# MotionDetectorCamera.net
KiCad netlist of a schematic drawn in EAGLE
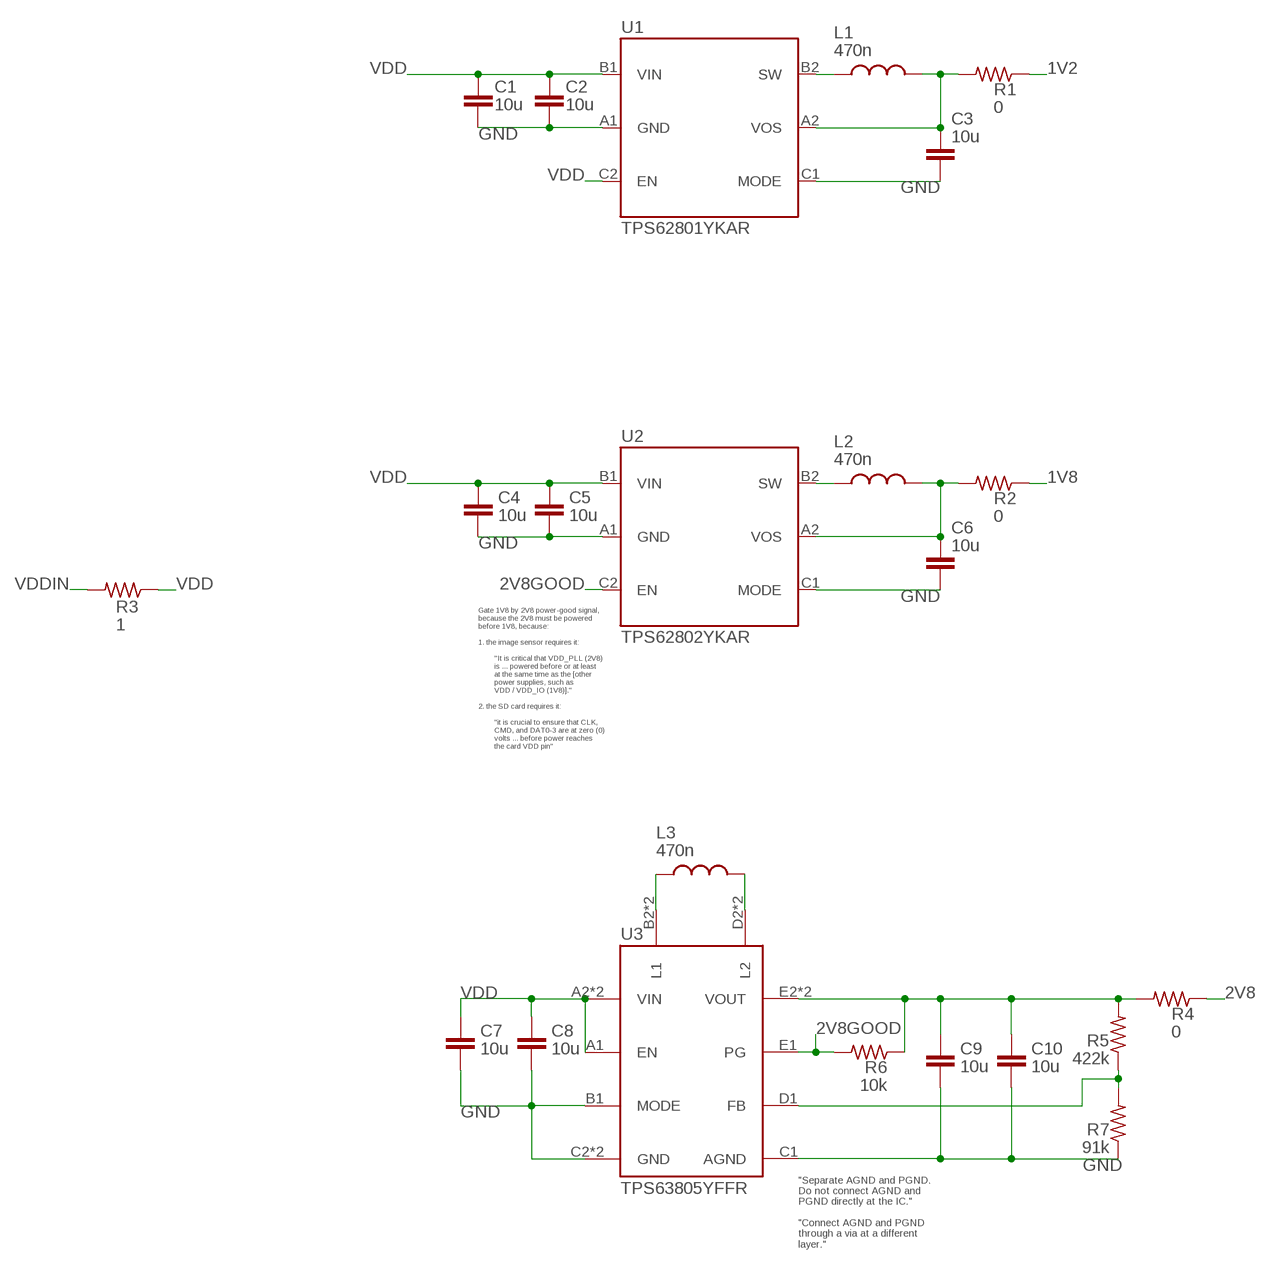
[diagram p0: schematic, sheet 1]
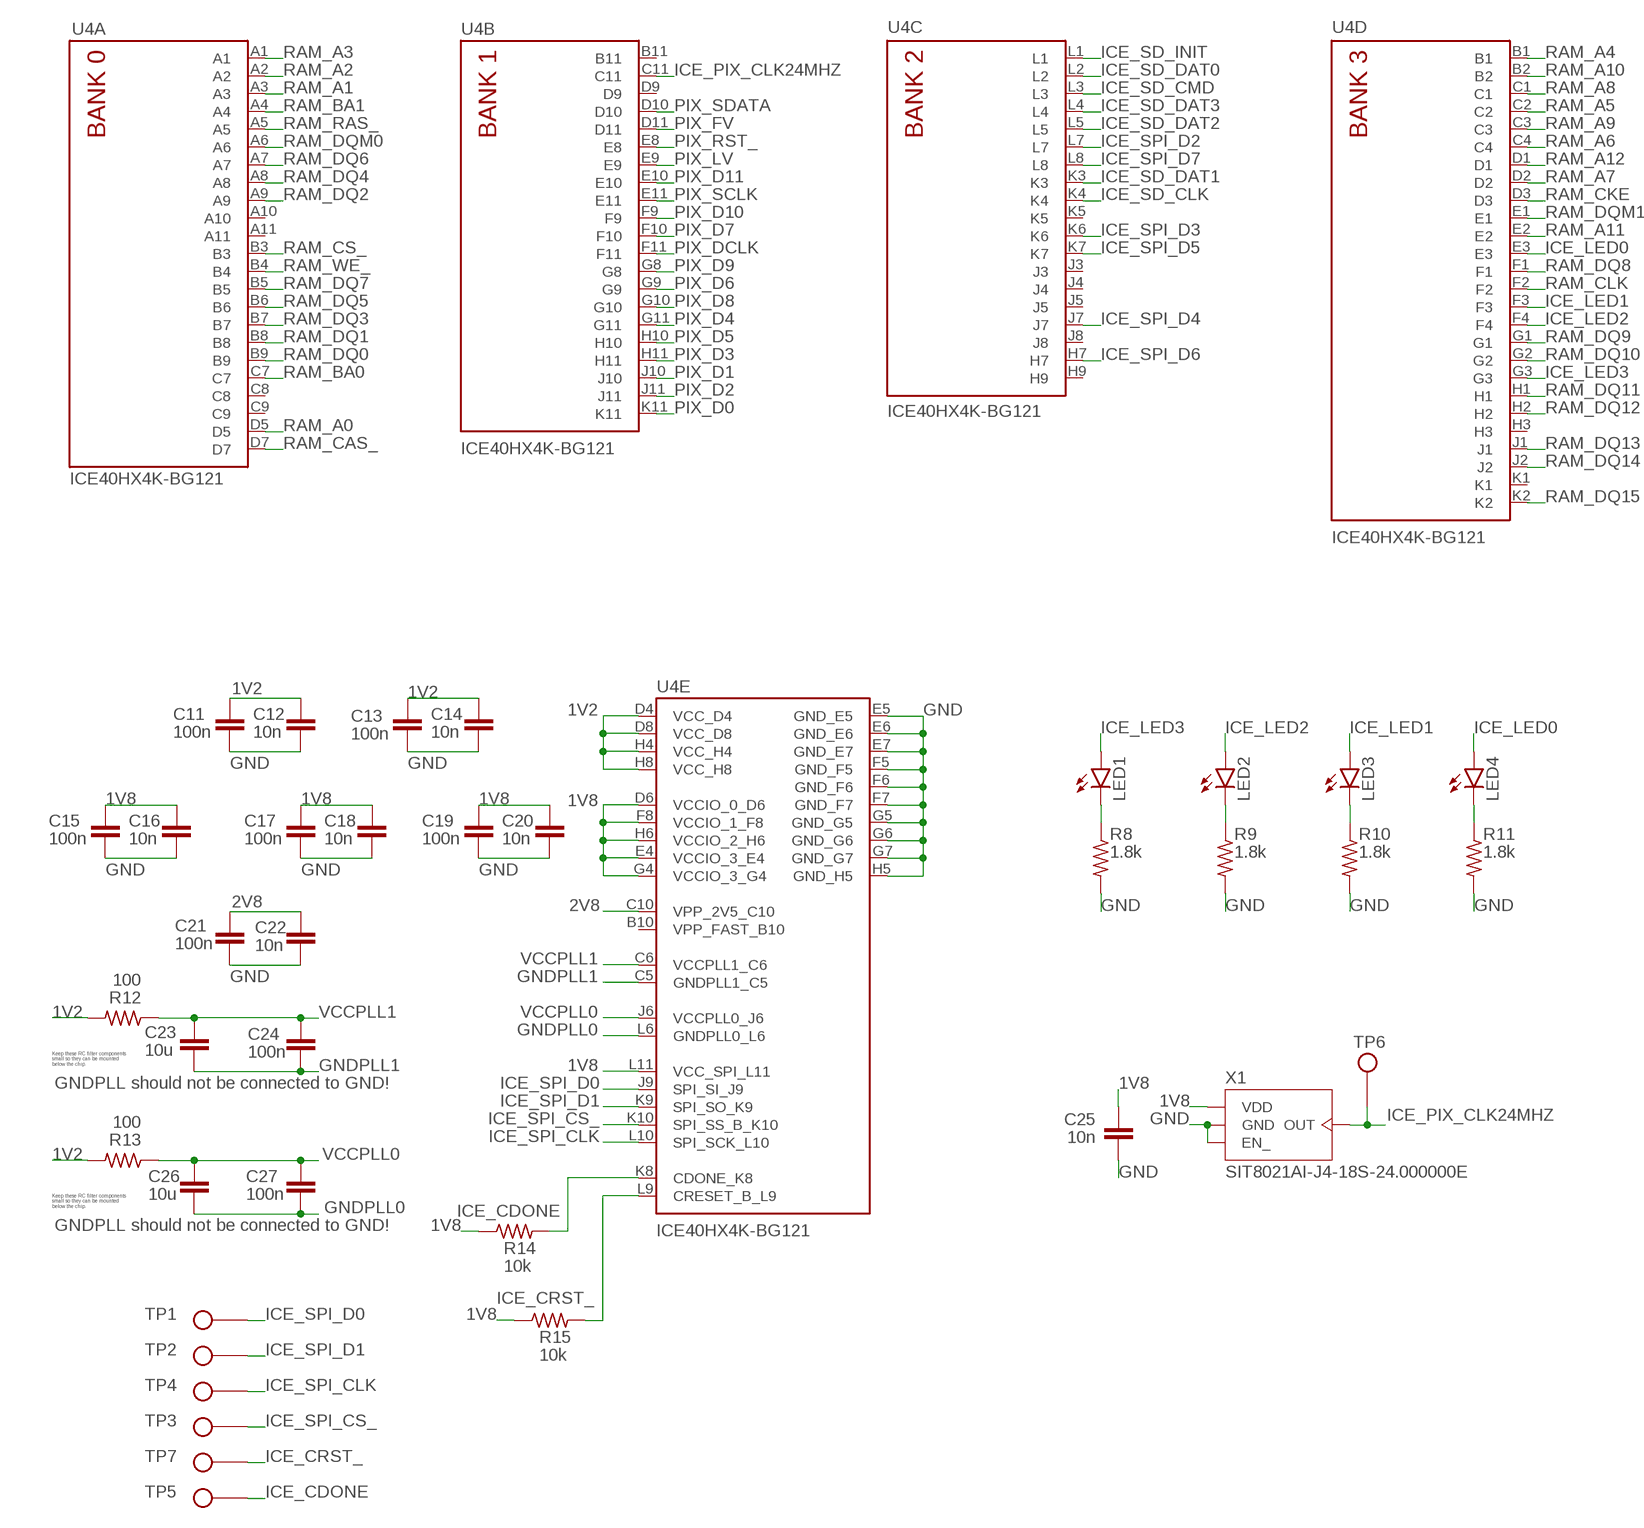
[diagram p1: schematic, sheet 2]
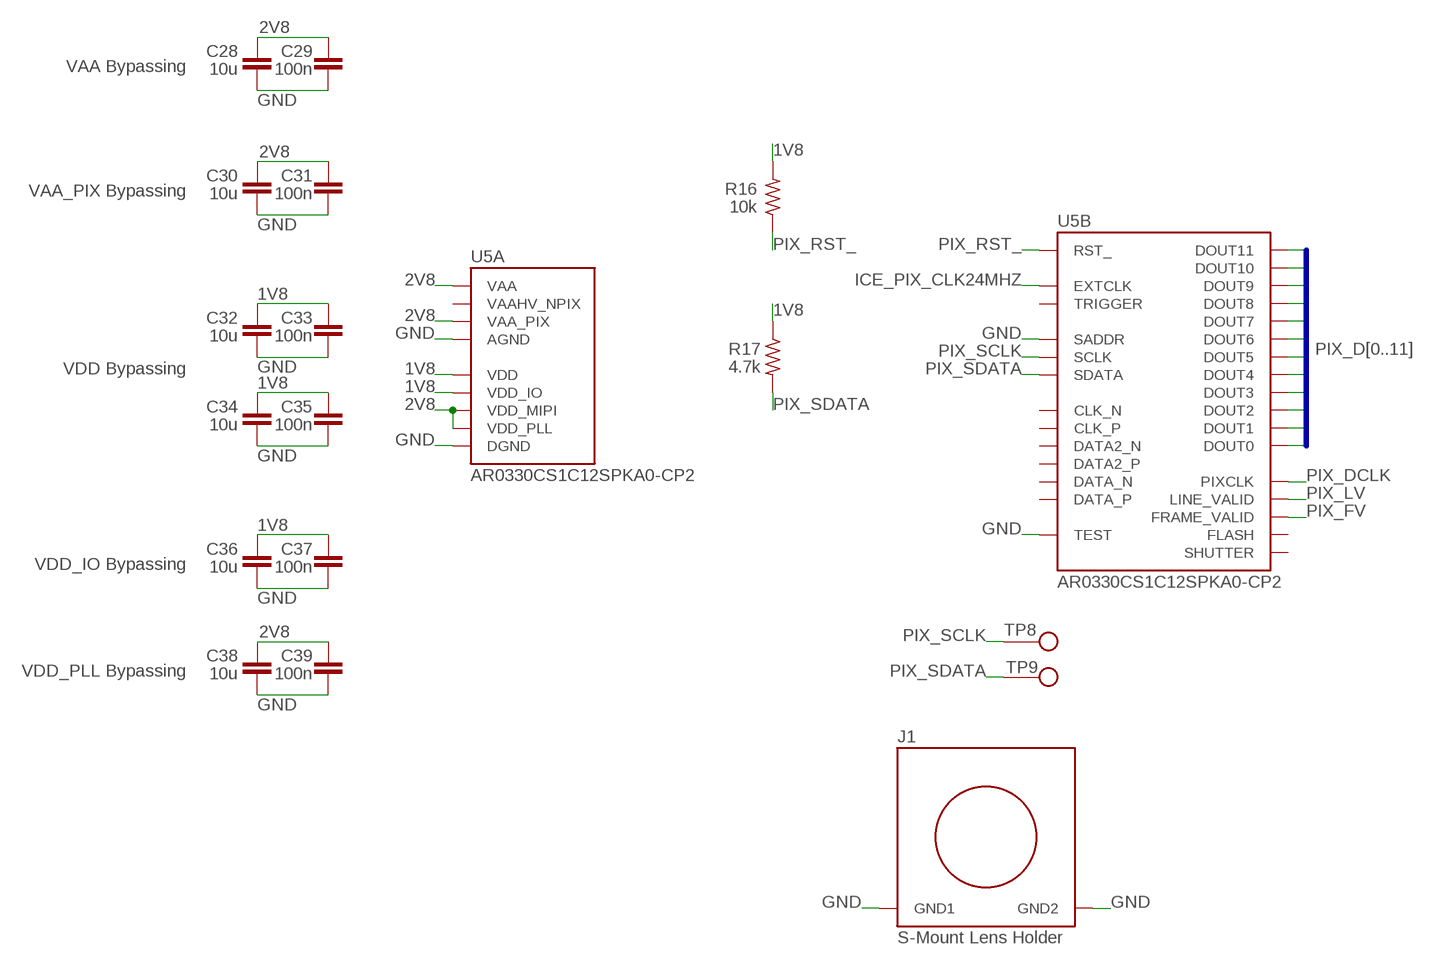
[diagram p2: schematic, sheet 3]
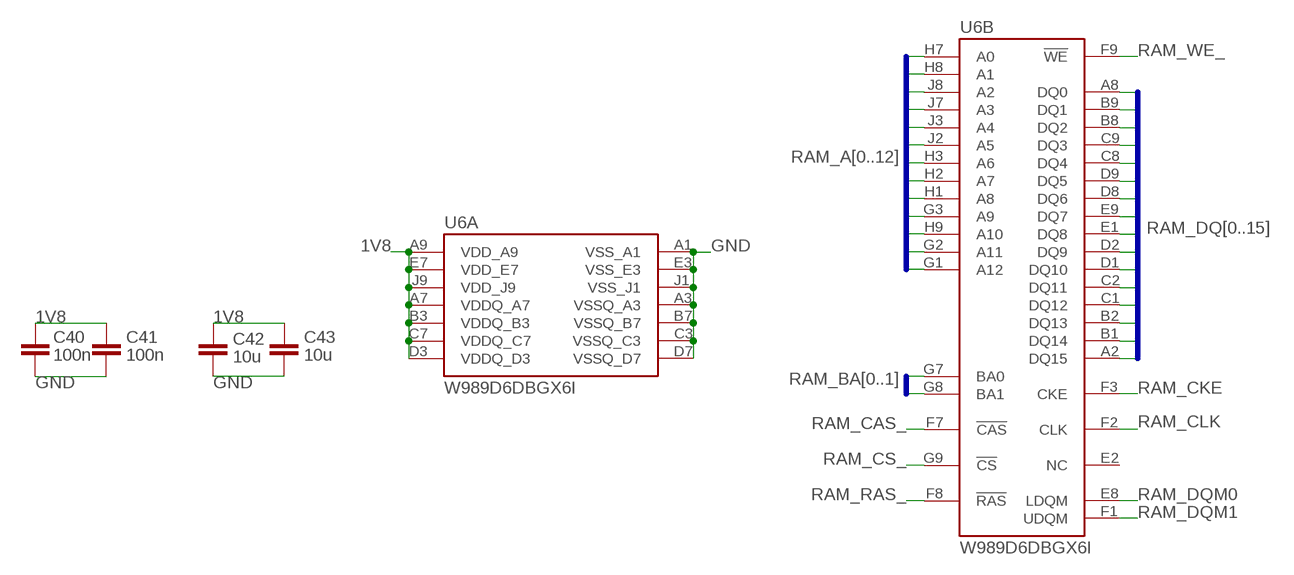
[diagram p3: schematic, sheet 4]
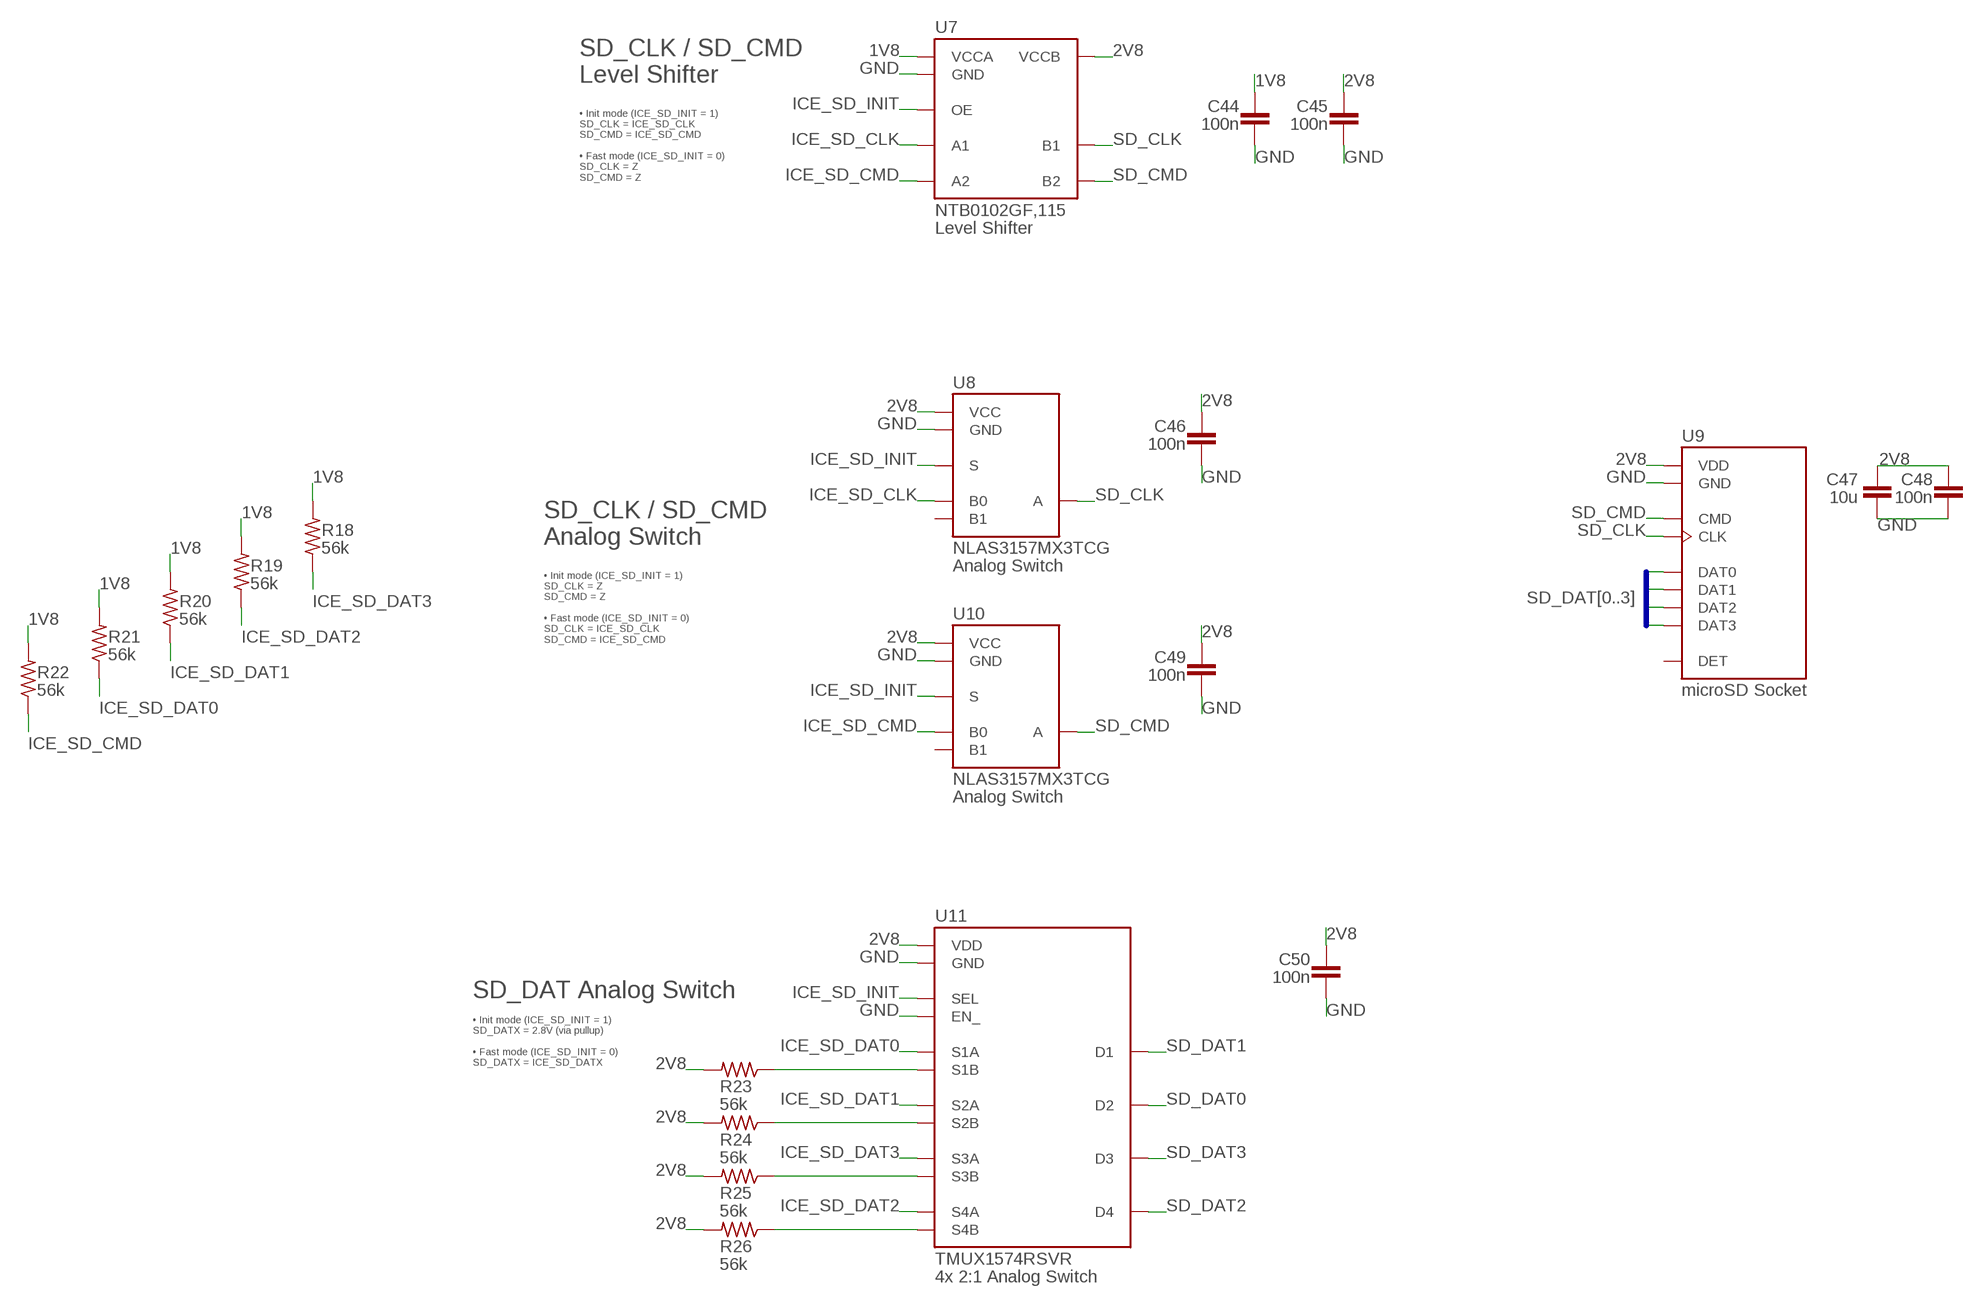
[diagram p4: schematic, sheet 5]
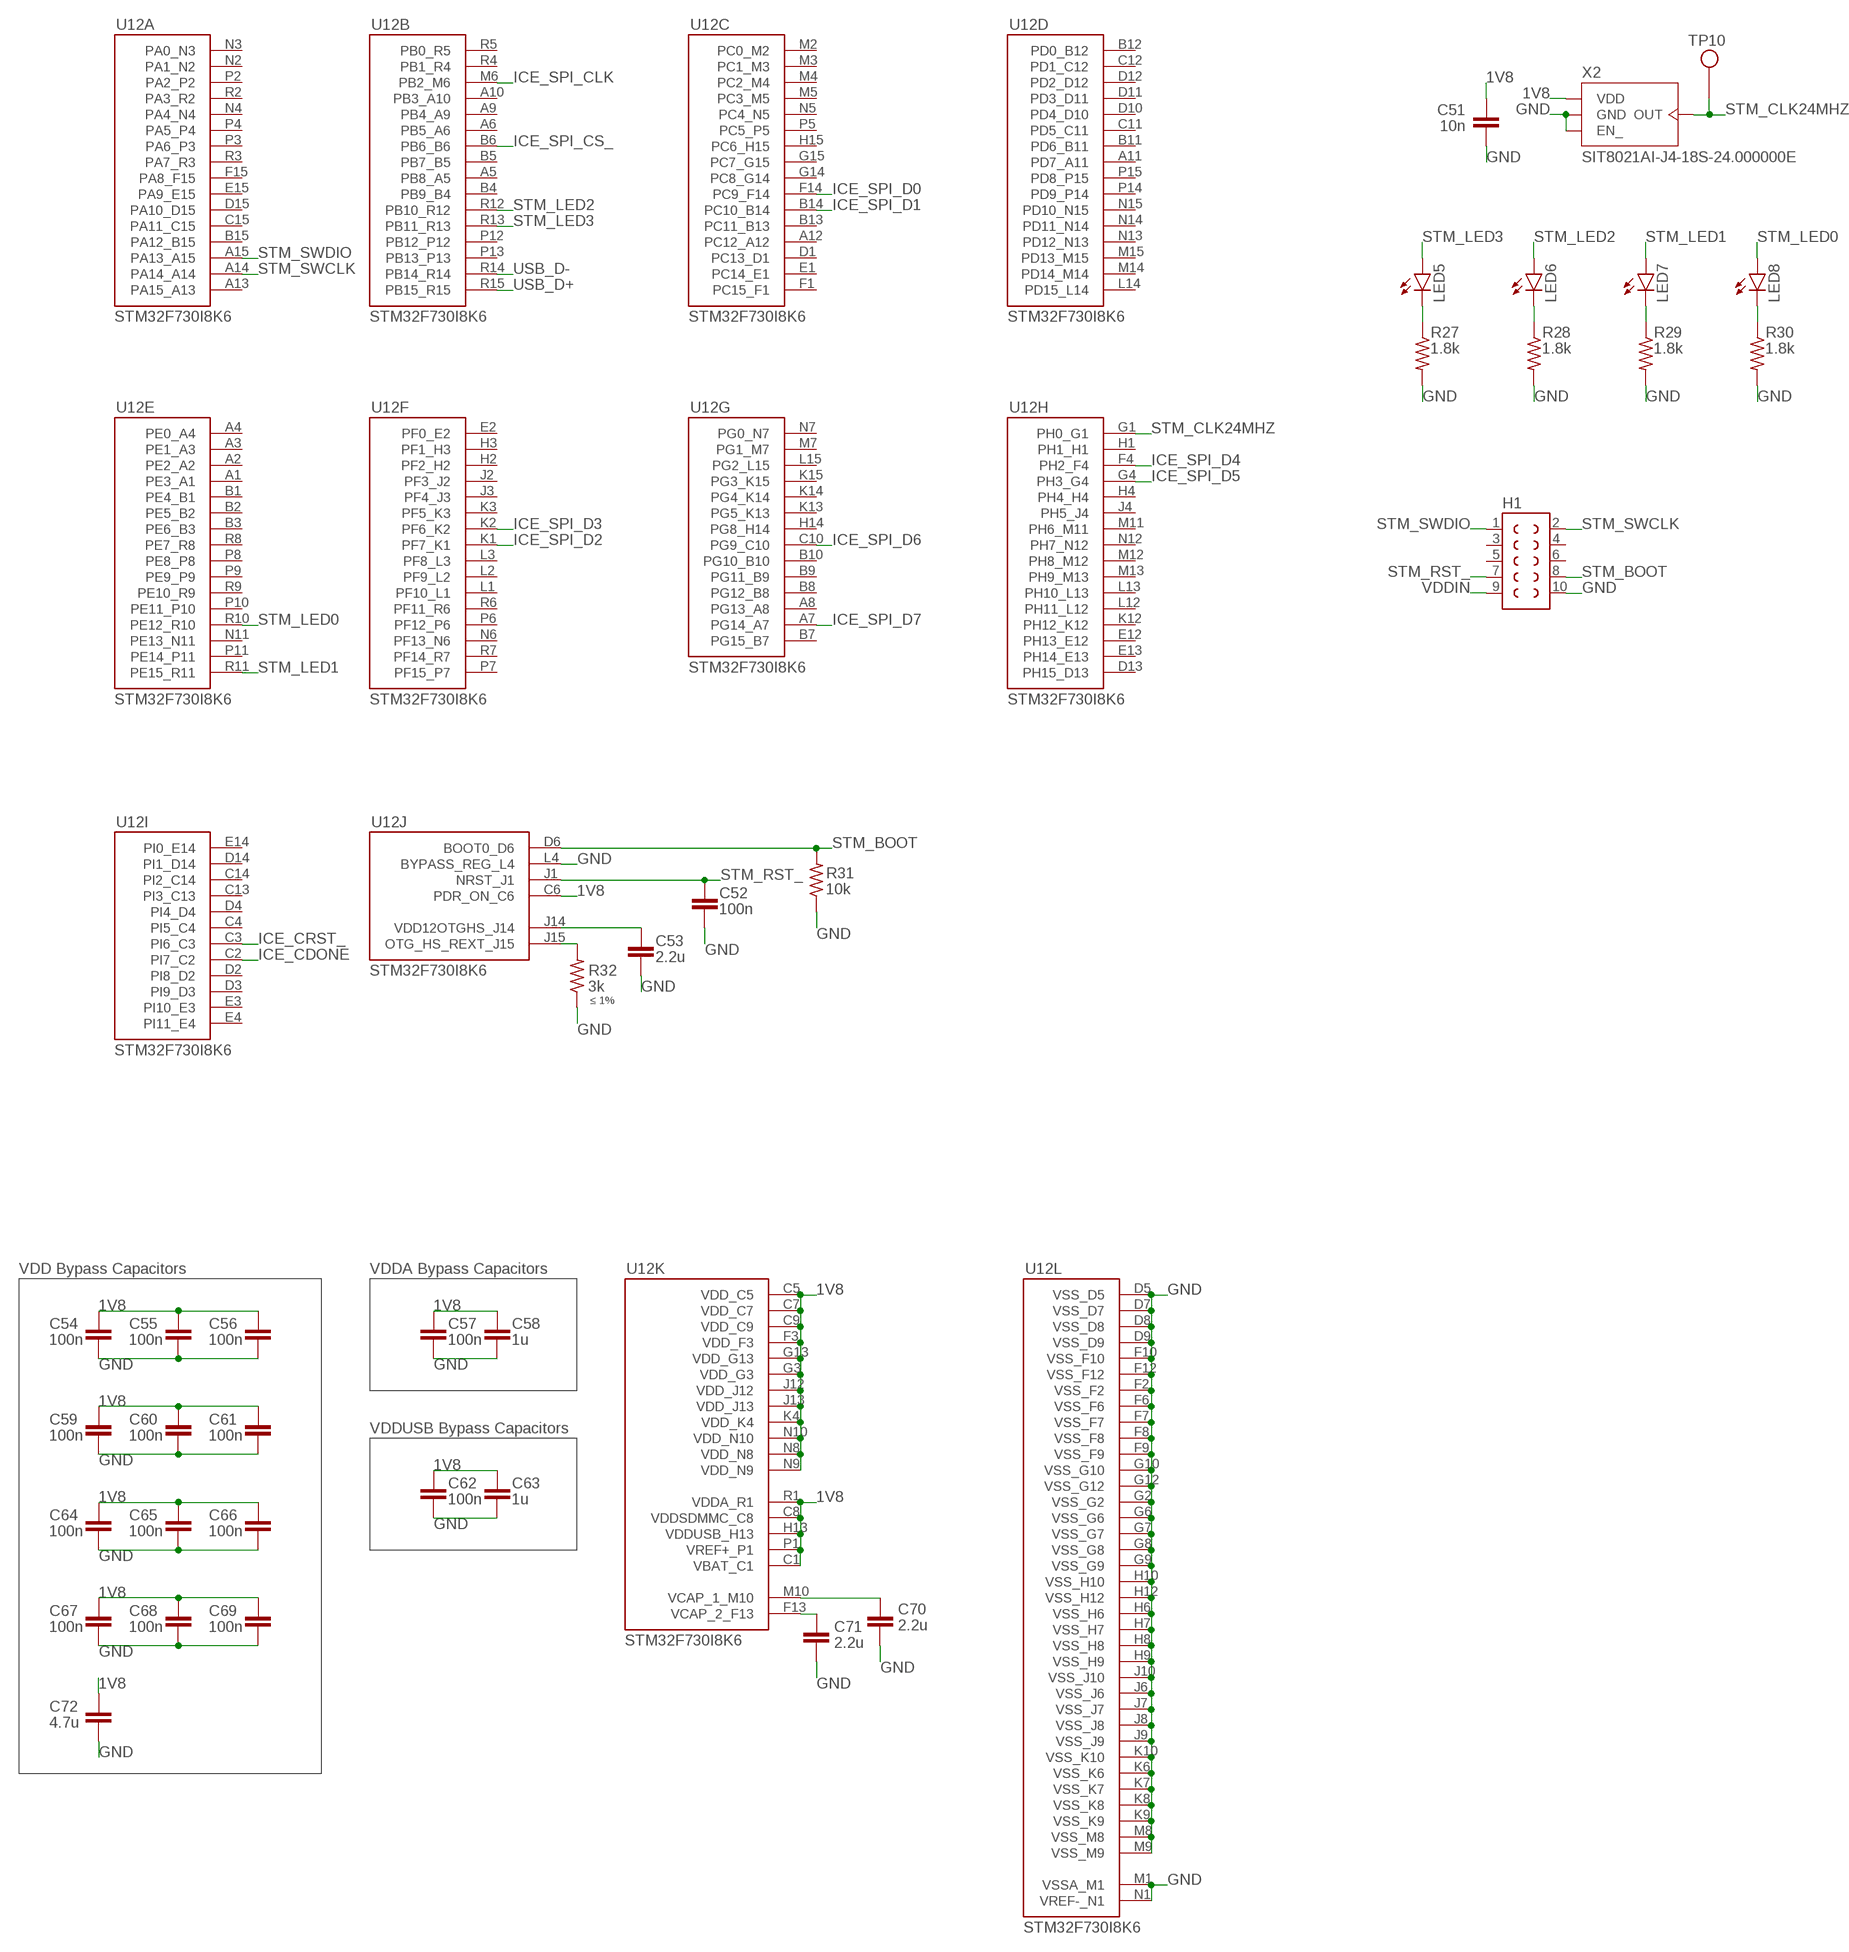
[diagram p5: schematic, sheet 6]
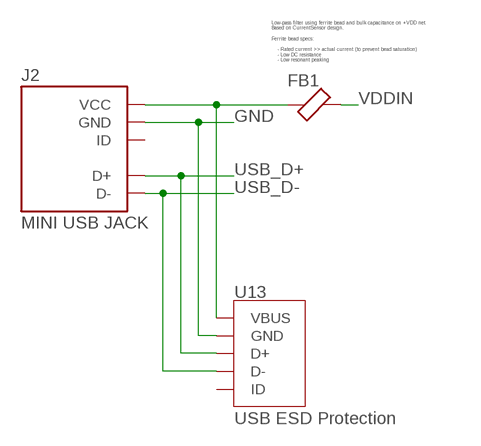
[diagram p6: schematic, sheet 7]

(export (version "E")
  (design (tool "Eeschema 10.0.6"))
  (components
    (comp (ref "C40")
      (value "100n")
      (footprint "eagle-import:0402")
      (fields (field (name "MFG") "Murata"))
      (libsource (lib "eagle-import") (part "CAPACITOR0402"))
    )
    (comp (ref "C41")
      (value "100n")
      (footprint "eagle-import:0402")
      (fields (field (name "MFG") "Murata"))
      (libsource (lib "eagle-import") (part "CAPACITOR0402"))
    )
    (comp (ref "C42")
      (value "10u")
      (footprint "eagle-import:0805")
      (fields (field (name "MFG") "KEMET"))
      (libsource (lib "eagle-import") (part "CAPACITOR0805"))
    )
    (comp (ref "C43")
      (value "10u")
      (footprint "eagle-import:0805")
      (fields (field (name "MFG") "KEMET"))
      (libsource (lib "eagle-import") (part "CAPACITOR0805"))
    )
    (comp (ref "U6")
      (value "W989D6DBGX6I")
      (footprint "eagle-import:W989D6DBGX6I")
      (fields (field (name "PN") "W989D6DBGX6I") (field (name "MFG") "Winbond"))
      (libsource (lib "eagle-import") (part "W989D6DBGX6I"))
    )
    (comp (ref "C11")
      (value "100n")
      (footprint "eagle-import:0402")
      (fields (field (name "MFG") "Murata"))
      (libsource (lib "eagle-import") (part "CAPACITOR0402"))
    )
    (comp (ref "C12")
      (value "10n")
      (footprint "eagle-import:0402")
      (fields (field (name "MFG") "Murata"))
      (libsource (lib "eagle-import") (part "CAPACITOR0402"))
    )
    (comp (ref "C13")
      (value "100n")
      (footprint "eagle-import:0402")
      (fields (field (name "MFG") "Murata"))
      (libsource (lib "eagle-import") (part "CAPACITOR0402"))
    )
    (comp (ref "C14")
      (value "10n")
      (footprint "eagle-import:0402")
      (fields (field (name "MFG") "Murata"))
      (libsource (lib "eagle-import") (part "CAPACITOR0402"))
    )
    (comp (ref "C15")
      (value "100n")
      (footprint "eagle-import:0402")
      (fields (field (name "MFG") "Murata"))
      (libsource (lib "eagle-import") (part "CAPACITOR0402"))
    )
    (comp (ref "C16")
      (value "10n")
      (footprint "eagle-import:0402")
      (fields (field (name "MFG") "Murata"))
      (libsource (lib "eagle-import") (part "CAPACITOR0402"))
    )
    (comp (ref "C17")
      (value "100n")
      (footprint "eagle-import:0402")
      (fields (field (name "MFG") "Murata"))
      (libsource (lib "eagle-import") (part "CAPACITOR0402"))
    )
    (comp (ref "C18")
      (value "10n")
      (footprint "eagle-import:0402")
      (fields (field (name "MFG") "Murata"))
      (libsource (lib "eagle-import") (part "CAPACITOR0402"))
    )
    (comp (ref "C19")
      (value "100n")
      (footprint "eagle-import:0402")
      (fields (field (name "MFG") "Murata"))
      (libsource (lib "eagle-import") (part "CAPACITOR0402"))
    )
    (comp (ref "C20")
      (value "10n")
      (footprint "eagle-import:0402")
      (fields (field (name "MFG") "Murata"))
      (libsource (lib "eagle-import") (part "CAPACITOR0402"))
    )
    (comp (ref "C21")
      (value "100n")
      (footprint "eagle-import:0402")
      (fields (field (name "MFG") "Murata"))
      (libsource (lib "eagle-import") (part "CAPACITOR0402"))
    )
    (comp (ref "C22")
      (value "10n")
      (footprint "eagle-import:0402")
      (fields (field (name "MFG") "Murata"))
      (libsource (lib "eagle-import") (part "CAPACITOR0402"))
    )
    (comp (ref "C23")
      (value "10u")
      (footprint "eagle-import:0805")
      (fields (field (name "MFG") "KEMET"))
      (libsource (lib "eagle-import") (part "CAPACITOR0805"))
    )
    (comp (ref "C24")
      (value "100n")
      (footprint "eagle-import:0402")
      (fields (field (name "MFG") "Murata"))
      (libsource (lib "eagle-import") (part "CAPACITOR0402"))
    )
    (comp (ref "C25")
      (value "10n")
      (footprint "eagle-import:0402")
      (fields (field (name "MFG") "Murata"))
      (libsource (lib "eagle-import") (part "CAPACITOR0402"))
    )
    (comp (ref "C26")
      (value "10u")
      (footprint "eagle-import:0805")
      (fields (field (name "MFG") "KEMET"))
      (libsource (lib "eagle-import") (part "CAPACITOR0805"))
    )
    (comp (ref "C27")
      (value "100n")
      (footprint "eagle-import:0402")
      (fields (field (name "MFG") "Murata"))
      (libsource (lib "eagle-import") (part "CAPACITOR0402"))
    )
    (comp (ref "LED1")
      (value "LED")
      (footprint "eagle-import:LED-0603")
      (fields (field (name "MFG") "OSRAM"))
      (libsource (lib "eagle-import") (part "LED"))
    )
    (comp (ref "LED2")
      (value "LED")
      (footprint "eagle-import:LED-0603")
      (fields (field (name "MFG") "OSRAM"))
      (libsource (lib "eagle-import") (part "LED"))
    )
    (comp (ref "LED3")
      (value "LED")
      (footprint "eagle-import:LED-0603")
      (fields (field (name "MFG") "OSRAM"))
      (libsource (lib "eagle-import") (part "LED"))
    )
    (comp (ref "LED4")
      (value "LED")
      (footprint "eagle-import:LED-0603")
      (fields (field (name "MFG") "OSRAM"))
      (libsource (lib "eagle-import") (part "LED"))
    )
    (comp (ref "R8")
      (value "1.8k")
      (footprint "eagle-import:0402")
      (fields (field (name "MFG") "TE Connectivity"))
      (libsource (lib "eagle-import") (part "RESISTOR0402"))
    )
    (comp (ref "R9")
      (value "1.8k")
      (footprint "eagle-import:0402")
      (fields (field (name "MFG") "TE Connectivity"))
      (libsource (lib "eagle-import") (part "RESISTOR0402"))
    )
    (comp (ref "R10")
      (value "1.8k")
      (footprint "eagle-import:0402")
      (fields (field (name "MFG") "TE Connectivity"))
      (libsource (lib "eagle-import") (part "RESISTOR0402"))
    )
    (comp (ref "R11")
      (value "1.8k")
      (footprint "eagle-import:0402")
      (fields (field (name "MFG") "TE Connectivity"))
      (libsource (lib "eagle-import") (part "RESISTOR0402"))
    )
    (comp (ref "R12")
      (value "100")
      (footprint "eagle-import:0402")
      (fields (field (name "MFG") "Bourns"))
      (libsource (lib "eagle-import") (part "RESISTOR0402"))
    )
    (comp (ref "R13")
      (value "100")
      (footprint "eagle-import:0402")
      (fields (field (name "MFG") "Bourns"))
      (libsource (lib "eagle-import") (part "RESISTOR0402"))
    )
    (comp (ref "R14")
      (value "10k")
      (footprint "eagle-import:0402")
      (fields (field (name "MFG") "Vishay"))
      (libsource (lib "eagle-import") (part "RESISTOR0402"))
    )
    (comp (ref "R15")
      (value "10k")
      (footprint "eagle-import:0402")
      (fields (field (name "MFG") "Vishay"))
      (libsource (lib "eagle-import") (part "RESISTOR0402"))
    )
    (comp (ref "TP1")
      (value "TEST-POINT")
      (footprint "eagle-import:TEST-POINT")
      (libsource (lib "eagle-import") (part "TEST-POINT"))
    )
    (comp (ref "TP2")
      (value "TEST-POINT")
      (footprint "eagle-import:TEST-POINT")
      (libsource (lib "eagle-import") (part "TEST-POINT"))
    )
    (comp (ref "TP3")
      (value "TEST-POINT")
      (footprint "eagle-import:TEST-POINT")
      (libsource (lib "eagle-import") (part "TEST-POINT"))
    )
    (comp (ref "TP4")
      (value "TEST-POINT")
      (footprint "eagle-import:TEST-POINT")
      (libsource (lib "eagle-import") (part "TEST-POINT"))
    )
    (comp (ref "TP5")
      (value "TEST-POINT")
      (footprint "eagle-import:TEST-POINT")
      (libsource (lib "eagle-import") (part "TEST-POINT"))
    )
    (comp (ref "TP6")
      (value "TEST-POINT")
      (footprint "eagle-import:TEST-POINT")
      (libsource (lib "eagle-import") (part "TEST-POINT"))
    )
    (comp (ref "TP7")
      (value "TEST-POINT")
      (footprint "eagle-import:TEST-POINT")
      (libsource (lib "eagle-import") (part "TEST-POINT"))
    )
    (comp (ref "U4")
      (value "LATTICE-ICE40HX4K-BG121")
      (footprint "eagle-import:LATTICE-ICE40HX4K-BG121")
      (fields (field (name "MFG") "Lattice"))
      (libsource (lib "eagle-import") (part "LATTICE-ICE40HX4K-BG121"))
    )
    (comp (ref "X1")
      (value "SITIME-SIT8021")
      (footprint "eagle-import:SITIME-SIT8021")
      (fields (field (name "MFG") "SiTime") (field (name "PN") "SIT8021AI-J4-18S-24.000000E"))
      (libsource (lib "eagle-import") (part "SITIME-SIT8021"))
    )
    (comp (ref "C51")
      (value "10n")
      (footprint "eagle-import:0402")
      (fields (field (name "MFG") "Murata"))
      (libsource (lib "eagle-import") (part "CAPACITOR0402"))
    )
    (comp (ref "C52")
      (value "100n")
      (footprint "eagle-import:0402")
      (fields (field (name "MFG") "Murata"))
      (libsource (lib "eagle-import") (part "CAPACITOR0402"))
    )
    (comp (ref "C53")
      (value "2.2u")
      (footprint "eagle-import:0402")
      (fields (field (name "MFG") "AVX"))
      (libsource (lib "eagle-import") (part "CAPACITOR0402"))
    )
    (comp (ref "C54")
      (value "100n")
      (footprint "eagle-import:0402")
      (fields (field (name "MFG") "Murata"))
      (libsource (lib "eagle-import") (part "CAPACITOR0402"))
    )
    (comp (ref "C55")
      (value "100n")
      (footprint "eagle-import:0402")
      (fields (field (name "MFG") "Murata"))
      (libsource (lib "eagle-import") (part "CAPACITOR0402"))
    )
    (comp (ref "C56")
      (value "100n")
      (footprint "eagle-import:0402")
      (fields (field (name "MFG") "Murata"))
      (libsource (lib "eagle-import") (part "CAPACITOR0402"))
    )
    (comp (ref "C57")
      (value "100n")
      (footprint "eagle-import:0402")
      (fields (field (name "MFG") "Murata"))
      (libsource (lib "eagle-import") (part "CAPACITOR0402"))
    )
    (comp (ref "C58")
      (value "1u")
      (footprint "eagle-import:0402")
      (fields (field (name "MFG") "Taiyo Yuden"))
      (libsource (lib "eagle-import") (part "CAPACITOR0402"))
    )
    (comp (ref "C59")
      (value "100n")
      (footprint "eagle-import:0402")
      (fields (field (name "MFG") "Murata"))
      (libsource (lib "eagle-import") (part "CAPACITOR0402"))
    )
    (comp (ref "C60")
      (value "100n")
      (footprint "eagle-import:0402")
      (fields (field (name "MFG") "Murata"))
      (libsource (lib "eagle-import") (part "CAPACITOR0402"))
    )
    (comp (ref "C61")
      (value "100n")
      (footprint "eagle-import:0402")
      (fields (field (name "MFG") "Murata"))
      (libsource (lib "eagle-import") (part "CAPACITOR0402"))
    )
    (comp (ref "C62")
      (value "100n")
      (footprint "eagle-import:0402")
      (fields (field (name "MFG") "Murata"))
      (libsource (lib "eagle-import") (part "CAPACITOR0402"))
    )
    (comp (ref "C63")
      (value "1u")
      (footprint "eagle-import:0402")
      (fields (field (name "MFG") "Taiyo Yuden"))
      (libsource (lib "eagle-import") (part "CAPACITOR0402"))
    )
    (comp (ref "C64")
      (value "100n")
      (footprint "eagle-import:0402")
      (fields (field (name "MFG") "Murata"))
      (libsource (lib "eagle-import") (part "CAPACITOR0402"))
    )
    (comp (ref "C65")
      (value "100n")
      (footprint "eagle-import:0402")
      (fields (field (name "MFG") "Murata"))
      (libsource (lib "eagle-import") (part "CAPACITOR0402"))
    )
    (comp (ref "C66")
      (value "100n")
      (footprint "eagle-import:0402")
      (fields (field (name "MFG") "Murata"))
      (libsource (lib "eagle-import") (part "CAPACITOR0402"))
    )
    (comp (ref "C67")
      (value "100n")
      (footprint "eagle-import:0402")
      (fields (field (name "MFG") "Murata"))
      (libsource (lib "eagle-import") (part "CAPACITOR0402"))
    )
    (comp (ref "C68")
      (value "100n")
      (footprint "eagle-import:0402")
      (fields (field (name "MFG") "Murata"))
      (libsource (lib "eagle-import") (part "CAPACITOR0402"))
    )
    (comp (ref "C69")
      (value "100n")
      (footprint "eagle-import:0402")
      (fields (field (name "MFG") "Murata"))
      (libsource (lib "eagle-import") (part "CAPACITOR0402"))
    )
    (comp (ref "C70")
      (value "2.2u")
      (footprint "eagle-import:0402")
      (fields (field (name "MFG") "AVX"))
      (libsource (lib "eagle-import") (part "CAPACITOR0402"))
    )
    (comp (ref "C71")
      (value "2.2u")
      (footprint "eagle-import:0402")
      (fields (field (name "MFG") "AVX"))
      (libsource (lib "eagle-import") (part "CAPACITOR0402"))
    )
    (comp (ref "C72")
      (value "4.7u")
      (footprint "eagle-import:0603")
      (fields (field (name "MFG") "Taiyo Yuden"))
      (libsource (lib "eagle-import") (part "CAPACITOR0603"))
    )
    (comp (ref "H1")
      (value "HEADER-2X5")
      (footprint "eagle-import:TEC-1-2314844-0")
      (fields (field (name "MFG") "TE Connectivity"))
      (libsource (lib "eagle-import") (part "HEADER-2X5"))
    )
    (comp (ref "LED5")
      (value "LED")
      (footprint "eagle-import:LED-0603")
      (fields (field (name "MFG") "OSRAM"))
      (libsource (lib "eagle-import") (part "LED"))
    )
    (comp (ref "LED6")
      (value "LED")
      (footprint "eagle-import:LED-0603")
      (fields (field (name "MFG") "OSRAM"))
      (libsource (lib "eagle-import") (part "LED"))
    )
    (comp (ref "LED7")
      (value "LED")
      (footprint "eagle-import:LED-0603")
      (fields (field (name "MFG") "OSRAM"))
      (libsource (lib "eagle-import") (part "LED"))
    )
    (comp (ref "LED8")
      (value "LED")
      (footprint "eagle-import:LED-0603")
      (fields (field (name "MFG") "OSRAM"))
      (libsource (lib "eagle-import") (part "LED"))
    )
    (comp (ref "R27")
      (value "1.8k")
      (footprint "eagle-import:0402")
      (fields (field (name "MFG") "TE Connectivity"))
      (libsource (lib "eagle-import") (part "RESISTOR0402"))
    )
    (comp (ref "R28")
      (value "1.8k")
      (footprint "eagle-import:0402")
      (fields (field (name "MFG") "TE Connectivity"))
      (libsource (lib "eagle-import") (part "RESISTOR0402"))
    )
    (comp (ref "R29")
      (value "1.8k")
      (footprint "eagle-import:0402")
      (fields (field (name "MFG") "TE Connectivity"))
      (libsource (lib "eagle-import") (part "RESISTOR0402"))
    )
    (comp (ref "R30")
      (value "1.8k")
      (footprint "eagle-import:0402")
      (fields (field (name "MFG") "TE Connectivity"))
      (libsource (lib "eagle-import") (part "RESISTOR0402"))
    )
    (comp (ref "R31")
      (value "10k")
      (footprint "eagle-import:0402")
      (fields (field (name "MFG") "Vishay"))
      (libsource (lib "eagle-import") (part "RESISTOR0402"))
    )
    (comp (ref "R32")
      (value "3k")
      (footprint "eagle-import:0402")
      (fields (field (name "MFG") "Yageo"))
      (libsource (lib "eagle-import") (part "RESISTOR0402"))
    )
    (comp (ref "TP10")
      (value "TEST-POINT")
      (footprint "eagle-import:TEST-POINT")
      (libsource (lib "eagle-import") (part "TEST-POINT"))
    )
    (comp (ref "U12")
      (value "STM-STM32F730")
      (footprint "eagle-import:STM-STM32F730I8")
      (fields (field (name "MFG") "STMicroelectronics") (field (name "PN") "STM32F730I8K6"))
      (libsource (lib "eagle-import") (part "STM-STM32F730"))
    )
    (comp (ref "X2")
      (value "SITIME-SIT8021")
      (footprint "eagle-import:SITIME-SIT8021")
      (fields (field (name "MFG") "SiTime") (field (name "PN") "SIT8021AI-J4-18S-24.000000E"))
      (libsource (lib "eagle-import") (part "SITIME-SIT8021"))
    )
    (comp (ref "C44")
      (value "100n")
      (footprint "eagle-import:0402")
      (fields (field (name "MFG") "Murata"))
      (libsource (lib "eagle-import") (part "CAPACITOR0402"))
    )
    (comp (ref "C45")
      (value "100n")
      (footprint "eagle-import:0402")
      (fields (field (name "MFG") "Murata"))
      (libsource (lib "eagle-import") (part "CAPACITOR0402"))
    )
    (comp (ref "C46")
      (value "100n")
      (footprint "eagle-import:0402")
      (fields (field (name "MFG") "Murata"))
      (libsource (lib "eagle-import") (part "CAPACITOR0402"))
    )
    (comp (ref "C47")
      (value "10u")
      (footprint "eagle-import:0805")
      (fields (field (name "MFG") "KEMET"))
      (libsource (lib "eagle-import") (part "CAPACITOR0805"))
    )
    (comp (ref "C48")
      (value "100n")
      (footprint "eagle-import:0402")
      (fields (field (name "MFG") "Murata"))
      (libsource (lib "eagle-import") (part "CAPACITOR0402"))
    )
    (comp (ref "C49")
      (value "100n")
      (footprint "eagle-import:0402")
      (fields (field (name "MFG") "Murata"))
      (libsource (lib "eagle-import") (part "CAPACITOR0402"))
    )
    (comp (ref "C50")
      (value "100n")
      (footprint "eagle-import:0402")
      (fields (field (name "MFG") "Murata"))
      (libsource (lib "eagle-import") (part "CAPACITOR0402"))
    )
    (comp (ref "R18")
      (value "56k")
      (footprint "eagle-import:0402")
      (fields (field (name "MFG") "Yageo"))
      (libsource (lib "eagle-import") (part "RESISTOR0402"))
    )
    (comp (ref "R19")
      (value "56k")
      (footprint "eagle-import:0402")
      (fields (field (name "MFG") "Yageo"))
      (libsource (lib "eagle-import") (part "RESISTOR0402"))
    )
    (comp (ref "R20")
      (value "56k")
      (footprint "eagle-import:0402")
      (fields (field (name "MFG") "Yageo"))
      (libsource (lib "eagle-import") (part "RESISTOR0402"))
    )
    (comp (ref "R21")
      (value "56k")
      (footprint "eagle-import:0402")
      (fields (field (name "MFG") "Yageo"))
      (libsource (lib "eagle-import") (part "RESISTOR0402"))
    )
    (comp (ref "R22")
      (value "56k")
      (footprint "eagle-import:0402")
      (fields (field (name "MFG") "Yageo"))
      (libsource (lib "eagle-import") (part "RESISTOR0402"))
    )
    (comp (ref "R23")
      (value "56k")
      (footprint "eagle-import:0402")
      (fields (field (name "MFG") "Yageo"))
      (libsource (lib "eagle-import") (part "RESISTOR0402"))
    )
    (comp (ref "R24")
      (value "56k")
      (footprint "eagle-import:0402")
      (fields (field (name "MFG") "Yageo"))
      (libsource (lib "eagle-import") (part "RESISTOR0402"))
    )
    (comp (ref "R25")
      (value "56k")
      (footprint "eagle-import:0402")
      (fields (field (name "MFG") "Yageo"))
      (libsource (lib "eagle-import") (part "RESISTOR0402"))
    )
    (comp (ref "R26")
      (value "56k")
      (footprint "eagle-import:0402")
      (fields (field (name "MFG") "Yageo"))
      (libsource (lib "eagle-import") (part "RESISTOR0402"))
    )
    (comp (ref "U7")
      (value "NXP-NTB0102")
      (footprint "eagle-import:NXP-NTB0102GF")
      (fields
        (field (name "PN") "NTB0102GF")
        (field (name "MFG") "NXP")
        (field (name "PN_1") "NTB0102GF,115")
      )
      (libsource (lib "eagle-import") (part "NXP-NTB0102"))
    )
    (comp (ref "U8")
      (value "ON-NLAS3157")
      (footprint "eagle-import:ON-NLAS3157MX3TCG")
      (fields (field (name "PN") "NLAS3157MX3TCG") (field (name "MFG") "ON Semiconductor"))
      (libsource (lib "eagle-import") (part "ON-NLAS3157"))
    )
    (comp (ref "U9")
      (value "MICROSD-SOCKET")
      (footprint "eagle-import:MOLEX-1051620001")
      (fields (field (name "MFG") "Molex"))
      (libsource (lib "eagle-import") (part "MICROSD-SOCKET"))
    )
    (comp (ref "U10")
      (value "ON-NLAS3157")
      (footprint "eagle-import:ON-NLAS3157MX3TCG")
      (fields (field (name "PN") "NLAS3157MX3TCG") (field (name "MFG") "ON Semiconductor"))
      (libsource (lib "eagle-import") (part "ON-NLAS3157"))
    )
    (comp (ref "U11")
      (value "TI-TMUX1574")
      (footprint "eagle-import:TI-TMUX1574RSVR")
      (fields (field (name "PN") "TMUX1574RSVR") (field (name "MFG") "Texas Instruments"))
      (libsource (lib "eagle-import") (part "TI-TMUX1574"))
    )
    (comp (ref "C28")
      (value "10u")
      (footprint "eagle-import:0805")
      (fields (field (name "MFG") "KEMET"))
      (libsource (lib "eagle-import") (part "CAPACITOR0805"))
    )
    (comp (ref "C29")
      (value "100n")
      (footprint "eagle-import:0402")
      (fields (field (name "MFG") "Murata"))
      (libsource (lib "eagle-import") (part "CAPACITOR0402"))
    )
    (comp (ref "C30")
      (value "10u")
      (footprint "eagle-import:0805")
      (fields (field (name "MFG") "KEMET"))
      (libsource (lib "eagle-import") (part "CAPACITOR0805"))
    )
    (comp (ref "C31")
      (value "100n")
      (footprint "eagle-import:0402")
      (fields (field (name "MFG") "Murata"))
      (libsource (lib "eagle-import") (part "CAPACITOR0402"))
    )
    (comp (ref "C32")
      (value "10u")
      (footprint "eagle-import:0805")
      (fields (field (name "MFG") "KEMET"))
      (libsource (lib "eagle-import") (part "CAPACITOR0805"))
    )
    (comp (ref "C33")
      (value "100n")
      (footprint "eagle-import:0402")
      (fields (field (name "MFG") "Murata"))
      (libsource (lib "eagle-import") (part "CAPACITOR0402"))
    )
    (comp (ref "C34")
      (value "10u")
      (footprint "eagle-import:0805")
      (fields (field (name "MFG") "KEMET"))
      (libsource (lib "eagle-import") (part "CAPACITOR0805"))
    )
    (comp (ref "C35")
      (value "100n")
      (footprint "eagle-import:0402")
      (fields (field (name "MFG") "Murata"))
      (libsource (lib "eagle-import") (part "CAPACITOR0402"))
    )
    (comp (ref "C36")
      (value "10u")
      (footprint "eagle-import:0805")
      (fields (field (name "MFG") "KEMET"))
      (libsource (lib "eagle-import") (part "CAPACITOR0805"))
    )
    (comp (ref "C37")
      (value "100n")
      (footprint "eagle-import:0402")
      (fields (field (name "MFG") "Murata"))
      (libsource (lib "eagle-import") (part "CAPACITOR0402"))
    )
    (comp (ref "C38")
      (value "10u")
      (footprint "eagle-import:0805")
      (fields (field (name "MFG") "KEMET"))
      (libsource (lib "eagle-import") (part "CAPACITOR0805"))
    )
    (comp (ref "C39")
      (value "100n")
      (footprint "eagle-import:0402")
      (fields (field (name "MFG") "Murata"))
      (libsource (lib "eagle-import") (part "CAPACITOR0402"))
    )
    (comp (ref "J1")
      (value "S-MOUNT-LENS-HOLDER")
      (footprint "eagle-import:S-MOUNT-LENS-HOLDER")
      (fields (field (name "MFG") "Marshall Electronics"))
      (libsource (lib "eagle-import") (part "S-MOUNT-LENS-HOLDER"))
    )
    (comp (ref "R16")
      (value "10k")
      (footprint "eagle-import:0402")
      (fields (field (name "MFG") "Vishay"))
      (libsource (lib "eagle-import") (part "RESISTOR0402"))
    )
    (comp (ref "R17")
      (value "4.7k")
      (footprint "eagle-import:0402")
      (fields (field (name "MFG") "Vishay"))
      (libsource (lib "eagle-import") (part "RESISTOR0402"))
    )
    (comp (ref "TP8")
      (value "TEST-POINT")
      (footprint "eagle-import:TEST-POINT")
      (libsource (lib "eagle-import") (part "TEST-POINT"))
    )
    (comp (ref "TP9")
      (value "TEST-POINT")
      (footprint "eagle-import:TEST-POINT")
      (libsource (lib "eagle-import") (part "TEST-POINT"))
    )
    (comp (ref "U5")
      (value "ON-AR0330CS1C12SPKA0")
      (footprint "eagle-import:ON-AR0330CS1C12SPKA0")
      (fields
        (field (name "PN") "AR0330CS1C12SPKA0")
        (field (name "MFG") "ON Semiconductor")
        (field (name "PN_1") "AR0330CS1C12SPKA0-CP2")
      )
      (libsource (lib "eagle-import") (part "ON-AR0330CS1C12SPKA0"))
    )
    (comp (ref "FB1")
      (value "FERRITE-BEAD0402")
      (footprint "eagle-import:0402")
      (fields (field (name "MFG") "Taiyo Yuden"))
      (libsource (lib "eagle-import") (part "FERRITE-BEAD0402"))
    )
    (comp (ref "J2")
      (value "MINI-USB-JACK")
      (footprint "eagle-import:AMPHENOLFCI-10033526-N3222MLF")
      (fields (field (name "MFG") "Amphenol FCI"))
      (libsource (lib "eagle-import") (part "MINI-USB-JACK"))
    )
    (comp (ref "U13")
      (value "TI-TPD4S012DRYR")
      (footprint "eagle-import:TI-TPD4S012DRYR")
      (fields (field (name "MFG") "Texas Instruments"))
      (libsource (lib "eagle-import") (part "TI-TPD4S012DRYR"))
    )
    (comp (ref "C1")
      (value "10u")
      (footprint "eagle-import:0805")
      (fields (field (name "MFG") "KEMET"))
      (libsource (lib "eagle-import") (part "CAPACITOR0805"))
    )
    (comp (ref "C2")
      (value "10u")
      (footprint "eagle-import:0805")
      (fields (field (name "MFG") "KEMET"))
      (libsource (lib "eagle-import") (part "CAPACITOR0805"))
    )
    (comp (ref "C3")
      (value "10u")
      (footprint "eagle-import:0805")
      (fields (field (name "MFG") "KEMET"))
      (libsource (lib "eagle-import") (part "CAPACITOR0805"))
    )
    (comp (ref "C4")
      (value "10u")
      (footprint "eagle-import:0805")
      (fields (field (name "MFG") "KEMET"))
      (libsource (lib "eagle-import") (part "CAPACITOR0805"))
    )
    (comp (ref "C5")
      (value "10u")
      (footprint "eagle-import:0805")
      (fields (field (name "MFG") "KEMET"))
      (libsource (lib "eagle-import") (part "CAPACITOR0805"))
    )
    (comp (ref "C6")
      (value "10u")
      (footprint "eagle-import:0805")
      (fields (field (name "MFG") "KEMET"))
      (libsource (lib "eagle-import") (part "CAPACITOR0805"))
    )
    (comp (ref "C7")
      (value "10u")
      (footprint "eagle-import:0805")
      (fields (field (name "MFG") "KEMET"))
      (libsource (lib "eagle-import") (part "CAPACITOR0805"))
    )
    (comp (ref "C8")
      (value "10u")
      (footprint "eagle-import:0805")
      (fields (field (name "MFG") "KEMET"))
      (libsource (lib "eagle-import") (part "CAPACITOR0805"))
    )
    (comp (ref "C9")
      (value "10u")
      (footprint "eagle-import:0805")
      (fields (field (name "MFG") "KEMET"))
      (libsource (lib "eagle-import") (part "CAPACITOR0805"))
    )
    (comp (ref "C10")
      (value "10u")
      (footprint "eagle-import:0805")
      (fields (field (name "MFG") "KEMET"))
      (libsource (lib "eagle-import") (part "CAPACITOR0805"))
    )
    (comp (ref "L1")
      (value "470n")
      (footprint "eagle-import:0806")
      (fields (field (name "MFG") "Murata"))
      (libsource (lib "eagle-import") (part "INDUCTOR0806"))
    )
    (comp (ref "L2")
      (value "470n")
      (footprint "eagle-import:0806")
      (fields (field (name "MFG") "Murata"))
      (libsource (lib "eagle-import") (part "INDUCTOR0806"))
    )
    (comp (ref "L3")
      (value "470n")
      (footprint "eagle-import:0806")
      (fields (field (name "MFG") "Murata"))
      (libsource (lib "eagle-import") (part "INDUCTOR0806"))
    )
    (comp (ref "R1")
      (value "0")
      (footprint "eagle-import:0805")
      (fields (field (name "MFG") "Vishay"))
      (libsource (lib "eagle-import") (part "RESISTOR0805"))
    )
    (comp (ref "R2")
      (value "0")
      (footprint "eagle-import:0805")
      (fields (field (name "MFG") "Vishay"))
      (libsource (lib "eagle-import") (part "RESISTOR0805"))
    )
    (comp (ref "R3")
      (value "1")
      (footprint "eagle-import:1206")
      (fields (field (name "MFG") "Vishay"))
      (libsource (lib "eagle-import") (part "RESISTOR1206"))
    )
    (comp (ref "R4")
      (value "0")
      (footprint "eagle-import:0805")
      (fields (field (name "MFG") "Vishay"))
      (libsource (lib "eagle-import") (part "RESISTOR0805"))
    )
    (comp (ref "R5")
      (value "422k")
      (footprint "eagle-import:0402")
      (fields (field (name "MFG") "Bourns"))
      (libsource (lib "eagle-import") (part "RESISTOR0402"))
    )
    (comp (ref "R6")
      (value "10k")
      (footprint "eagle-import:0402")
      (fields (field (name "MFG") "Vishay"))
      (libsource (lib "eagle-import") (part "RESISTOR0402"))
    )
    (comp (ref "R7")
      (value "91k")
      (footprint "eagle-import:0402")
      (fields (field (name "MFG") "Bourns"))
      (libsource (lib "eagle-import") (part "RESISTOR0402"))
    )
    (comp (ref "U1")
      (value "TI-TPS6280XYKAR")
      (footprint "eagle-import:TI-TPS6280XYKAR")
      (fields (field (name "MFG") "Texas Instruments") (field (name "PN") "TPS62801YKAR"))
      (libsource (lib "eagle-import") (part "TI-TPS6280XYKAR"))
    )
    (comp (ref "U2")
      (value "TI-TPS6280XYKAR")
      (footprint "eagle-import:TI-TPS6280XYKAR")
      (fields (field (name "MFG") "Texas Instruments") (field (name "PN") "TPS62802YKAR"))
      (libsource (lib "eagle-import") (part "TI-TPS6280XYKAR"))
    )
    (comp (ref "U3")
      (value "TI-TPS63805YFFR")
      (footprint "eagle-import:TI-TPS63805YFFR")
      (fields (field (name "PN") "TPS63805YFFR") (field (name "MFG") "Texas Instruments"))
      (libsource (lib "eagle-import") (part "TI-TPS63805YFFR"))
    )
  )
  (nets
    (net (code "6") (name "1V2") (class "Default")
      (node (ref "C11") (pin "1") (pinfunction "1_1") (pintype "bidirectional"))
      (node (ref "C12") (pin "1") (pinfunction "1_1") (pintype "bidirectional"))
      (node (ref "C13") (pin "1") (pinfunction "1_1") (pintype "bidirectional"))
      (node (ref "C14") (pin "1") (pinfunction "1_1") (pintype "bidirectional"))
      (node (ref "R1") (pin "1") (pinfunction "1_1") (pintype "bidirectional"))
      (node (ref "R12") (pin "2") (pinfunction "2_2") (pintype "bidirectional"))
      (node (ref "R13") (pin "2") (pinfunction "2_2") (pintype "bidirectional"))
      (node (ref "U4") (pin "D4") (pinfunction "VCC_D4_D4") (pintype "bidirectional"))
      (node (ref "U4") (pin "D8") (pinfunction "VCC_D8_D8") (pintype "bidirectional"))
      (node (ref "U4") (pin "H4") (pinfunction "VCC_H4_H4") (pintype "bidirectional"))
      (node (ref "U4") (pin "H8") (pinfunction "VCC_H8_H8") (pintype "bidirectional"))
    )
    (net (code "7") (name "1V8") (class "Default")
      (node (ref "C15") (pin "1") (pinfunction "1_1") (pintype "bidirectional"))
      (node (ref "C16") (pin "1") (pinfunction "1_1") (pintype "bidirectional"))
      (node (ref "C17") (pin "1") (pinfunction "1_1") (pintype "bidirectional"))
      (node (ref "C18") (pin "1") (pinfunction "1_1") (pintype "bidirectional"))
      (node (ref "C19") (pin "1") (pinfunction "1_1") (pintype "bidirectional"))
      (node (ref "C20") (pin "1") (pinfunction "1_1") (pintype "bidirectional"))
      (node (ref "C25") (pin "1") (pinfunction "1_1") (pintype "bidirectional"))
      (node (ref "C32") (pin "1") (pinfunction "1_1") (pintype "bidirectional"))
      (node (ref "C33") (pin "1") (pinfunction "1_1") (pintype "bidirectional"))
      (node (ref "C34") (pin "1") (pinfunction "1_1") (pintype "bidirectional"))
      (node (ref "C35") (pin "1") (pinfunction "1_1") (pintype "bidirectional"))
      (node (ref "C36") (pin "1") (pinfunction "1_1") (pintype "bidirectional"))
      (node (ref "C37") (pin "1") (pinfunction "1_1") (pintype "bidirectional"))
      (node (ref "C40") (pin "1") (pinfunction "1_1") (pintype "bidirectional"))
      (node (ref "C41") (pin "1") (pinfunction "1_1") (pintype "bidirectional"))
      (node (ref "C42") (pin "1") (pinfunction "1_1") (pintype "bidirectional"))
      (node (ref "C43") (pin "1") (pinfunction "1_1") (pintype "bidirectional"))
      (node (ref "C44") (pin "1") (pinfunction "1_1") (pintype "bidirectional"))
      (node (ref "C51") (pin "1") (pinfunction "1_1") (pintype "bidirectional"))
      (node (ref "C54") (pin "1") (pinfunction "1_1") (pintype "bidirectional"))
      (node (ref "C55") (pin "1") (pinfunction "1_1") (pintype "bidirectional"))
      (node (ref "C56") (pin "1") (pinfunction "1_1") (pintype "bidirectional"))
      (node (ref "C57") (pin "1") (pinfunction "1_1") (pintype "bidirectional"))
      (node (ref "C58") (pin "1") (pinfunction "1_1") (pintype "bidirectional"))
      (node (ref "C59") (pin "1") (pinfunction "1_1") (pintype "bidirectional"))
      (node (ref "C60") (pin "1") (pinfunction "1_1") (pintype "bidirectional"))
      (node (ref "C61") (pin "1") (pinfunction "1_1") (pintype "bidirectional"))
      (node (ref "C62") (pin "1") (pinfunction "1_1") (pintype "bidirectional"))
      (node (ref "C63") (pin "1") (pinfunction "1_1") (pintype "bidirectional"))
      (node (ref "C64") (pin "1") (pinfunction "1_1") (pintype "bidirectional"))
      (node (ref "C65") (pin "1") (pinfunction "1_1") (pintype "bidirectional"))
      (node (ref "C66") (pin "1") (pinfunction "1_1") (pintype "bidirectional"))
      (node (ref "C67") (pin "1") (pinfunction "1_1") (pintype "bidirectional"))
      (node (ref "C68") (pin "1") (pinfunction "1_1") (pintype "bidirectional"))
      (node (ref "C69") (pin "1") (pinfunction "1_1") (pintype "bidirectional"))
      (node (ref "C72") (pin "1") (pinfunction "1_1") (pintype "bidirectional"))
      (node (ref "R14") (pin "1") (pinfunction "1_1") (pintype "bidirectional"))
      (node (ref "R15") (pin "1") (pinfunction "1_1") (pintype "bidirectional"))
      (node (ref "R16") (pin "2") (pinfunction "2_2") (pintype "bidirectional"))
      (node (ref "R17") (pin "1") (pinfunction "1_1") (pintype "bidirectional"))
      (node (ref "R18") (pin "2") (pinfunction "2_2") (pintype "bidirectional"))
      (node (ref "R19") (pin "2") (pinfunction "2_2") (pintype "bidirectional"))
      (node (ref "R2") (pin "1") (pinfunction "1_1") (pintype "bidirectional"))
      (node (ref "R20") (pin "2") (pinfunction "2_2") (pintype "bidirectional"))
      (node (ref "R21") (pin "2") (pinfunction "2_2") (pintype "bidirectional"))
      (node (ref "R22") (pin "2") (pinfunction "2_2") (pintype "bidirectional"))
      (node (ref "U12") (pin "C1") (pinfunction "VBAT_C1_C1") (pintype "bidirectional"))
      (node (ref "U12") (pin "C5") (pinfunction "VDD_C5_C5") (pintype "bidirectional"))
      (node (ref "U12") (pin "C6") (pinfunction "PDR_ON_C6_C6") (pintype "bidirectional"))
      (node (ref "U12") (pin "C7") (pinfunction "VDD_C7_C7") (pintype "bidirectional"))
      (node (ref "U12") (pin "C8") (pinfunction "VDDSDMMC_C8_C8") (pintype "bidirectional"))
      (node (ref "U12") (pin "C9") (pinfunction "VDD_C9_C9") (pintype "bidirectional"))
      (node (ref "U12") (pin "F3") (pinfunction "VDD_F3_F3") (pintype "bidirectional"))
      (node (ref "U12") (pin "G13") (pinfunction "VDD_G13_G13") (pintype "bidirectional"))
      (node (ref "U12") (pin "G3") (pinfunction "VDD_G3_G3") (pintype "bidirectional"))
      (node (ref "U12") (pin "H13") (pinfunction "VDDUSB_H13_H13") (pintype "bidirectional"))
      (node (ref "U12") (pin "J12") (pinfunction "VDD_J12_J12") (pintype "bidirectional"))
      (node (ref "U12") (pin "J13") (pinfunction "VDD_J13_J13") (pintype "bidirectional"))
      (node (ref "U12") (pin "K4") (pinfunction "VDD_K4_K4") (pintype "bidirectional"))
      (node (ref "U12") (pin "N10") (pinfunction "VDD_N10_N10") (pintype "bidirectional"))
      (node (ref "U12") (pin "N8") (pinfunction "VDD_N8_N8") (pintype "bidirectional"))
      (node (ref "U12") (pin "N9") (pinfunction "VDD_N9_N9") (pintype "bidirectional"))
      (node (ref "U12") (pin "P1") (pinfunction "VREF+_P1_P1") (pintype "bidirectional"))
      (node (ref "U12") (pin "R1") (pinfunction "VDDA_R1_R1") (pintype "bidirectional"))
      (node (ref "U4") (pin "D6") (pinfunction "VCCIO_0_D6_D6") (pintype "bidirectional"))
      (node (ref "U4") (pin "E4") (pinfunction "VCCIO_3_E4_E4") (pintype "bidirectional"))
      (node (ref "U4") (pin "F8") (pinfunction "VCCIO_1_F8_F8") (pintype "bidirectional"))
      (node (ref "U4") (pin "G4") (pinfunction "VCCIO_3_G4_G4") (pintype "bidirectional"))
      (node (ref "U4") (pin "H6") (pinfunction "VCCIO_2_H6_H6") (pintype "bidirectional"))
      (node (ref "U4") (pin "L11") (pinfunction "VCC_SPI_L11_L11") (pintype "bidirectional"))
      (node (ref "U5") (pin "A7") (pinfunction "VDD_IO_A7") (pintype "bidirectional"))
      (node (ref "U5") (pin "A8") (pinfunction "VDD_A8") (pintype "bidirectional"))
      (node (ref "U5") (pin "B1") (pinfunction "VDD_B1") (pintype "bidirectional"))
      (node (ref "U5") (pin "D2") (pinfunction "VDD_IO_D2") (pintype "bidirectional"))
      (node (ref "U5") (pin "D5") (pinfunction "VDD_IO_D5") (pintype "bidirectional"))
      (node (ref "U5") (pin "D6") (pinfunction "VDD_IO_D6") (pintype "bidirectional"))
      (node (ref "U5") (pin "E5") (pinfunction "VDD_IO_E5") (pintype "bidirectional"))
      (node (ref "U5") (pin "F6") (pinfunction "VDD_IO_F6") (pintype "bidirectional"))
      (node (ref "U5") (pin "G2") (pinfunction "VDD_G2") (pintype "bidirectional"))
      (node (ref "U5") (pin "G8") (pinfunction "VDD_G8") (pintype "bidirectional"))
      (node (ref "U5") (pin "H5") (pinfunction "VDD_IO_H5") (pintype "bidirectional"))
      (node (ref "U6") (pin "A7") (pinfunction "VDDQ_A7_A7") (pintype "bidirectional"))
      (node (ref "U6") (pin "A9") (pinfunction "VDD_A9_A9") (pintype "bidirectional"))
      (node (ref "U6") (pin "B3") (pinfunction "VDDQ_B3_B3") (pintype "bidirectional"))
      (node (ref "U6") (pin "C7") (pinfunction "VDDQ_C7_C7") (pintype "bidirectional"))
      (node (ref "U6") (pin "D3") (pinfunction "VDDQ_D3_D3") (pintype "bidirectional"))
      (node (ref "U6") (pin "E7") (pinfunction "VDD_E7_E7") (pintype "bidirectional"))
      (node (ref "U6") (pin "J9") (pinfunction "VDD_J9_J9") (pintype "bidirectional"))
      (node (ref "U7") (pin "3") (pinfunction "VCCA_3") (pintype "bidirectional"))
      (node (ref "X1") (pin "3") (pinfunction "VDD_3") (pintype "bidirectional"))
      (node (ref "X2") (pin "3") (pinfunction "VDD_3") (pintype "bidirectional"))
    )
    (net (code "8") (name "2V8") (class "Default")
      (node (ref "C21") (pin "1") (pinfunction "1_1") (pintype "bidirectional"))
      (node (ref "C22") (pin "1") (pinfunction "1_1") (pintype "bidirectional"))
      (node (ref "C28") (pin "1") (pinfunction "1_1") (pintype "bidirectional"))
      (node (ref "C29") (pin "1") (pinfunction "1_1") (pintype "bidirectional"))
      (node (ref "C30") (pin "1") (pinfunction "1_1") (pintype "bidirectional"))
      (node (ref "C31") (pin "1") (pinfunction "1_1") (pintype "bidirectional"))
      (node (ref "C38") (pin "1") (pinfunction "1_1") (pintype "bidirectional"))
      (node (ref "C39") (pin "1") (pinfunction "1_1") (pintype "bidirectional"))
      (node (ref "C45") (pin "1") (pinfunction "1_1") (pintype "bidirectional"))
      (node (ref "C46") (pin "1") (pinfunction "1_1") (pintype "bidirectional"))
      (node (ref "C47") (pin "1") (pinfunction "1_1") (pintype "bidirectional"))
      (node (ref "C48") (pin "1") (pinfunction "1_1") (pintype "bidirectional"))
      (node (ref "C49") (pin "1") (pinfunction "1_1") (pintype "bidirectional"))
      (node (ref "C50") (pin "1") (pinfunction "1_1") (pintype "bidirectional"))
      (node (ref "R23") (pin "2") (pinfunction "2_2") (pintype "bidirectional"))
      (node (ref "R24") (pin "2") (pinfunction "2_2") (pintype "bidirectional"))
      (node (ref "R25") (pin "2") (pinfunction "2_2") (pintype "bidirectional"))
      (node (ref "R26") (pin "2") (pinfunction "2_2") (pintype "bidirectional"))
      (node (ref "R4") (pin "1") (pinfunction "1_1") (pintype "bidirectional"))
      (node (ref "U10") (pin "1") (pinfunction "VCC_1") (pintype "bidirectional"))
      (node (ref "U11") (pin "14") (pinfunction "VDD_14") (pintype "bidirectional"))
      (node (ref "U4") (pin "C10") (pinfunction "VPP_2V5_C10_C10") (pintype "bidirectional"))
      (node (ref "U5") (pin "A1") (pinfunction "VAA_A1") (pintype "bidirectional"))
      (node (ref "U5") (pin "A5") (pinfunction "VAA_PIX_A5") (pintype "bidirectional"))
      (node (ref "U5") (pin "A6") (pinfunction "VAA_A6") (pintype "bidirectional"))
      (node (ref "U5") (pin "F8") (pinfunction "VDD_PLL_F8") (pintype "bidirectional"))
      (node (ref "U5") (pin "H6") (pinfunction "VDD_MIPI_H6") (pintype "bidirectional"))
      (node (ref "U5") (pin "H8") (pinfunction "VDD_MIPI_H8") (pintype "bidirectional"))
      (node (ref "U7") (pin "7") (pinfunction "VCCB_7") (pintype "bidirectional"))
      (node (ref "U8") (pin "1") (pinfunction "VCC_1") (pintype "bidirectional"))
      (node (ref "U9") (pin "VDD") (pinfunction "VDD_VDD") (pintype "bidirectional"))
    )
    (net (code "9") (name "2V8GOOD") (class "Default")
      (node (ref "R6") (pin "2") (pinfunction "2_2") (pintype "bidirectional"))
      (node (ref "U2") (pin "C2") (pinfunction "EN_C2") (pintype "bidirectional"))
      (node (ref "U3") (pin "E1") (pinfunction "PG_E1") (pintype "bidirectional"))
    )
    (net (code "10") (name "GND") (class "Default")
      (node (ref "C1") (pin "2") (pinfunction "2_2") (pintype "bidirectional"))
      (node (ref "C10") (pin "2") (pinfunction "2_2") (pintype "bidirectional"))
      (node (ref "C11") (pin "2") (pinfunction "2_2") (pintype "bidirectional"))
      (node (ref "C12") (pin "2") (pinfunction "2_2") (pintype "bidirectional"))
      (node (ref "C13") (pin "2") (pinfunction "2_2") (pintype "bidirectional"))
      (node (ref "C14") (pin "2") (pinfunction "2_2") (pintype "bidirectional"))
      (node (ref "C15") (pin "2") (pinfunction "2_2") (pintype "bidirectional"))
      (node (ref "C16") (pin "2") (pinfunction "2_2") (pintype "bidirectional"))
      (node (ref "C17") (pin "2") (pinfunction "2_2") (pintype "bidirectional"))
      (node (ref "C18") (pin "2") (pinfunction "2_2") (pintype "bidirectional"))
      (node (ref "C19") (pin "2") (pinfunction "2_2") (pintype "bidirectional"))
      (node (ref "C2") (pin "2") (pinfunction "2_2") (pintype "bidirectional"))
      (node (ref "C20") (pin "2") (pinfunction "2_2") (pintype "bidirectional"))
      (node (ref "C21") (pin "2") (pinfunction "2_2") (pintype "bidirectional"))
      (node (ref "C22") (pin "2") (pinfunction "2_2") (pintype "bidirectional"))
      (node (ref "C25") (pin "2") (pinfunction "2_2") (pintype "bidirectional"))
      (node (ref "C28") (pin "2") (pinfunction "2_2") (pintype "bidirectional"))
      (node (ref "C29") (pin "2") (pinfunction "2_2") (pintype "bidirectional"))
      (node (ref "C3") (pin "2") (pinfunction "2_2") (pintype "bidirectional"))
      (node (ref "C30") (pin "2") (pinfunction "2_2") (pintype "bidirectional"))
      (node (ref "C31") (pin "2") (pinfunction "2_2") (pintype "bidirectional"))
      (node (ref "C32") (pin "2") (pinfunction "2_2") (pintype "bidirectional"))
      (node (ref "C33") (pin "2") (pinfunction "2_2") (pintype "bidirectional"))
      (node (ref "C34") (pin "2") (pinfunction "2_2") (pintype "bidirectional"))
      (node (ref "C35") (pin "2") (pinfunction "2_2") (pintype "bidirectional"))
      (node (ref "C36") (pin "2") (pinfunction "2_2") (pintype "bidirectional"))
      (node (ref "C37") (pin "2") (pinfunction "2_2") (pintype "bidirectional"))
      (node (ref "C38") (pin "2") (pinfunction "2_2") (pintype "bidirectional"))
      (node (ref "C39") (pin "2") (pinfunction "2_2") (pintype "bidirectional"))
      (node (ref "C4") (pin "2") (pinfunction "2_2") (pintype "bidirectional"))
      (node (ref "C40") (pin "2") (pinfunction "2_2") (pintype "bidirectional"))
      (node (ref "C41") (pin "2") (pinfunction "2_2") (pintype "bidirectional"))
      (node (ref "C42") (pin "2") (pinfunction "2_2") (pintype "bidirectional"))
      (node (ref "C43") (pin "2") (pinfunction "2_2") (pintype "bidirectional"))
      (node (ref "C44") (pin "2") (pinfunction "2_2") (pintype "bidirectional"))
      (node (ref "C45") (pin "2") (pinfunction "2_2") (pintype "bidirectional"))
      (node (ref "C46") (pin "2") (pinfunction "2_2") (pintype "bidirectional"))
      (node (ref "C47") (pin "2") (pinfunction "2_2") (pintype "bidirectional"))
      (node (ref "C48") (pin "2") (pinfunction "2_2") (pintype "bidirectional"))
      (node (ref "C49") (pin "2") (pinfunction "2_2") (pintype "bidirectional"))
      (node (ref "C5") (pin "2") (pinfunction "2_2") (pintype "bidirectional"))
      (node (ref "C50") (pin "2") (pinfunction "2_2") (pintype "bidirectional"))
      (node (ref "C51") (pin "2") (pinfunction "2_2") (pintype "bidirectional"))
      (node (ref "C52") (pin "2") (pinfunction "2_2") (pintype "bidirectional"))
      (node (ref "C53") (pin "2") (pinfunction "2_2") (pintype "bidirectional"))
      (node (ref "C54") (pin "2") (pinfunction "2_2") (pintype "bidirectional"))
      (node (ref "C55") (pin "2") (pinfunction "2_2") (pintype "bidirectional"))
      (node (ref "C56") (pin "2") (pinfunction "2_2") (pintype "bidirectional"))
      (node (ref "C57") (pin "2") (pinfunction "2_2") (pintype "bidirectional"))
      (node (ref "C58") (pin "2") (pinfunction "2_2") (pintype "bidirectional"))
      (node (ref "C59") (pin "2") (pinfunction "2_2") (pintype "bidirectional"))
      (node (ref "C6") (pin "2") (pinfunction "2_2") (pintype "bidirectional"))
      (node (ref "C60") (pin "2") (pinfunction "2_2") (pintype "bidirectional"))
      (node (ref "C61") (pin "2") (pinfunction "2_2") (pintype "bidirectional"))
      (node (ref "C62") (pin "2") (pinfunction "2_2") (pintype "bidirectional"))
      (node (ref "C63") (pin "2") (pinfunction "2_2") (pintype "bidirectional"))
      (node (ref "C64") (pin "2") (pinfunction "2_2") (pintype "bidirectional"))
      (node (ref "C65") (pin "2") (pinfunction "2_2") (pintype "bidirectional"))
      (node (ref "C66") (pin "2") (pinfunction "2_2") (pintype "bidirectional"))
      (node (ref "C67") (pin "2") (pinfunction "2_2") (pintype "bidirectional"))
      (node (ref "C68") (pin "2") (pinfunction "2_2") (pintype "bidirectional"))
      (node (ref "C69") (pin "2") (pinfunction "2_2") (pintype "bidirectional"))
      (node (ref "C7") (pin "2") (pinfunction "2_2") (pintype "bidirectional"))
      (node (ref "C70") (pin "2") (pinfunction "2_2") (pintype "bidirectional"))
      (node (ref "C71") (pin "2") (pinfunction "2_2") (pintype "bidirectional"))
      (node (ref "C72") (pin "2") (pinfunction "2_2") (pintype "bidirectional"))
      (node (ref "C8") (pin "2") (pinfunction "2_2") (pintype "bidirectional"))
      (node (ref "C9") (pin "2") (pinfunction "2_2") (pintype "bidirectional"))
      (node (ref "H1") (pin "10") (pinfunction "10_10") (pintype "bidirectional"))
      (node (ref "J1") (pin "1") (pinfunction "GND1_1") (pintype "bidirectional"))
      (node (ref "J1") (pin "2") (pinfunction "GND2_2") (pintype "bidirectional"))
      (node (ref "J2") (pin "GND") (pinfunction "GND_GND") (pintype "bidirectional"))
      (node (ref "J2") (pin "GND2") (pinfunction "GND_GND2") (pintype "bidirectional"))
      (node (ref "J2") (pin "GND3") (pinfunction "GND_GND3") (pintype "bidirectional"))
      (node (ref "J2") (pin "GND4") (pinfunction "GND_GND4") (pintype "bidirectional"))
      (node (ref "J2") (pin "GND5") (pinfunction "GND_GND5") (pintype "bidirectional"))
      (node (ref "R10") (pin "2") (pinfunction "2_2") (pintype "bidirectional"))
      (node (ref "R11") (pin "2") (pinfunction "2_2") (pintype "bidirectional"))
      (node (ref "R27") (pin "2") (pinfunction "2_2") (pintype "bidirectional"))
      (node (ref "R28") (pin "2") (pinfunction "2_2") (pintype "bidirectional"))
      (node (ref "R29") (pin "2") (pinfunction "2_2") (pintype "bidirectional"))
      (node (ref "R30") (pin "2") (pinfunction "2_2") (pintype "bidirectional"))
      (node (ref "R31") (pin "1") (pinfunction "1_1") (pintype "bidirectional"))
      (node (ref "R32") (pin "1") (pinfunction "1_1") (pintype "bidirectional"))
      (node (ref "R7") (pin "1") (pinfunction "1_1") (pintype "bidirectional"))
      (node (ref "R8") (pin "2") (pinfunction "2_2") (pintype "bidirectional"))
      (node (ref "R9") (pin "2") (pinfunction "2_2") (pintype "bidirectional"))
      (node (ref "U1") (pin "A1") (pinfunction "GND_A1") (pintype "bidirectional"))
      (node (ref "U1") (pin "C1") (pinfunction "MODE_C1") (pintype "bidirectional"))
      (node (ref "U10") (pin "5") (pinfunction "GND_5") (pintype "bidirectional"))
      (node (ref "U11") (pin "13") (pinfunction "EN__13") (pintype "bidirectional"))
      (node (ref "U11") (pin "6") (pinfunction "GND_6") (pintype "bidirectional"))
      (node (ref "U12") (pin "D5") (pinfunction "VSS_D5_D5") (pintype "bidirectional"))
      (node (ref "U12") (pin "D7") (pinfunction "VSS_D7_D7") (pintype "bidirectional"))
      (node (ref "U12") (pin "D8") (pinfunction "VSS_D8_D8") (pintype "bidirectional"))
      (node (ref "U12") (pin "D9") (pinfunction "VSS_D9_D9") (pintype "bidirectional"))
      (node (ref "U12") (pin "F10") (pinfunction "VSS_F10_F10") (pintype "bidirectional"))
      (node (ref "U12") (pin "F12") (pinfunction "VSS_F12_F12") (pintype "bidirectional"))
      (node (ref "U12") (pin "F2") (pinfunction "VSS_F2_F2") (pintype "bidirectional"))
      (node (ref "U12") (pin "F6") (pinfunction "VSS_F6_F6") (pintype "bidirectional"))
      (node (ref "U12") (pin "F7") (pinfunction "VSS_F7_F7") (pintype "bidirectional"))
      (node (ref "U12") (pin "F8") (pinfunction "VSS_F8_F8") (pintype "bidirectional"))
      (node (ref "U12") (pin "F9") (pinfunction "VSS_F9_F9") (pintype "bidirectional"))
      (node (ref "U12") (pin "G10") (pinfunction "VSS_G10_G10") (pintype "bidirectional"))
      (node (ref "U12") (pin "G12") (pinfunction "VSS_G12_G12") (pintype "bidirectional"))
      (node (ref "U12") (pin "G2") (pinfunction "VSS_G2_G2") (pintype "bidirectional"))
      (node (ref "U12") (pin "G6") (pinfunction "VSS_G6_G6") (pintype "bidirectional"))
      (node (ref "U12") (pin "G7") (pinfunction "VSS_G7_G7") (pintype "bidirectional"))
      (node (ref "U12") (pin "G8") (pinfunction "VSS_G8_G8") (pintype "bidirectional"))
      (node (ref "U12") (pin "G9") (pinfunction "VSS_G9_G9") (pintype "bidirectional"))
      (node (ref "U12") (pin "H10") (pinfunction "VSS_H10_H10") (pintype "bidirectional"))
      (node (ref "U12") (pin "H12") (pinfunction "VSS_H12_H12") (pintype "bidirectional"))
      (node (ref "U12") (pin "H6") (pinfunction "VSS_H6_H6") (pintype "bidirectional"))
      (node (ref "U12") (pin "H7") (pinfunction "VSS_H7_H7") (pintype "bidirectional"))
      (node (ref "U12") (pin "H8") (pinfunction "VSS_H8_H8") (pintype "bidirectional"))
      (node (ref "U12") (pin "H9") (pinfunction "VSS_H9_H9") (pintype "bidirectional"))
      (node (ref "U12") (pin "J10") (pinfunction "VSS_J10_J10") (pintype "bidirectional"))
      (node (ref "U12") (pin "J6") (pinfunction "VSS_J6_J6") (pintype "bidirectional"))
      (node (ref "U12") (pin "J7") (pinfunction "VSS_J7_J7") (pintype "bidirectional"))
      (node (ref "U12") (pin "J8") (pinfunction "VSS_J8_J8") (pintype "bidirectional"))
      (node (ref "U12") (pin "J9") (pinfunction "VSS_J9_J9") (pintype "bidirectional"))
      (node (ref "U12") (pin "K10") (pinfunction "VSS_K10_K10") (pintype "bidirectional"))
      (node (ref "U12") (pin "K6") (pinfunction "VSS_K6_K6") (pintype "bidirectional"))
      (node (ref "U12") (pin "K7") (pinfunction "VSS_K7_K7") (pintype "bidirectional"))
      (node (ref "U12") (pin "K8") (pinfunction "VSS_K8_K8") (pintype "bidirectional"))
      (node (ref "U12") (pin "K9") (pinfunction "VSS_K9_K9") (pintype "bidirectional"))
      (node (ref "U12") (pin "L4") (pinfunction "BYPASS_REG_L4_L4") (pintype "bidirectional"))
      (node (ref "U12") (pin "M1") (pinfunction "VSSA_M1_M1") (pintype "bidirectional"))
      (node (ref "U12") (pin "M8") (pinfunction "VSS_M8_M8") (pintype "bidirectional"))
      (node (ref "U12") (pin "M9") (pinfunction "VSS_M9_M9") (pintype "bidirectional"))
      (node (ref "U12") (pin "N1") (pinfunction "VREF-_N1_N1") (pintype "bidirectional"))
      (node (ref "U13") (pin "4") (pinfunction "GND_4") (pintype "bidirectional"))
      (node (ref "U2") (pin "A1") (pinfunction "GND_A1") (pintype "bidirectional"))
      (node (ref "U2") (pin "C1") (pinfunction "MODE_C1") (pintype "bidirectional"))
      (node (ref "U3") (pin "B1") (pinfunction "MODE_B1") (pintype "bidirectional"))
      (node (ref "U3") (pin "C1") (pinfunction "AGND_C1") (pintype "bidirectional"))
      (node (ref "U3") (pin "C2") (pinfunction "GND_C2") (pintype "bidirectional"))
      (node (ref "U3") (pin "C3") (pinfunction "GND_C3") (pintype "bidirectional"))
      (node (ref "U4") (pin "E5") (pinfunction "GND_E5_E5") (pintype "bidirectional"))
      (node (ref "U4") (pin "E6") (pinfunction "GND_E6_E6") (pintype "bidirectional"))
      (node (ref "U4") (pin "E7") (pinfunction "GND_E7_E7") (pintype "bidirectional"))
      (node (ref "U4") (pin "F5") (pinfunction "GND_F5_F5") (pintype "bidirectional"))
      (node (ref "U4") (pin "F6") (pinfunction "GND_F6_F6") (pintype "bidirectional"))
      (node (ref "U4") (pin "F7") (pinfunction "GND_F7_F7") (pintype "bidirectional"))
      (node (ref "U4") (pin "G5") (pinfunction "GND_G5_G5") (pintype "bidirectional"))
      (node (ref "U4") (pin "G6") (pinfunction "GND_G6_G6") (pintype "bidirectional"))
      (node (ref "U4") (pin "G7") (pinfunction "GND_G7_G7") (pintype "bidirectional"))
      (node (ref "U4") (pin "H5") (pinfunction "GND_H5_H5") (pintype "bidirectional"))
      (node (ref "U5") (pin "A3") (pinfunction "AGND_A3") (pintype "bidirectional"))
      (node (ref "U5") (pin "B4") (pinfunction "DGND_B4") (pintype "bidirectional"))
      (node (ref "U5") (pin "B5") (pinfunction "AGND_B5") (pintype "bidirectional"))
      (node (ref "U5") (pin "B6") (pinfunction "DGND_B6") (pintype "bidirectional"))
      (node (ref "U5") (pin "B7") (pinfunction "TEST_B7") (pintype "bidirectional"))
      (node (ref "U5") (pin "C1") (pinfunction "SADDR_C1") (pintype "bidirectional"))
      (node (ref "U5") (pin "C4") (pinfunction "DGND_C4") (pintype "bidirectional"))
      (node (ref "U5") (pin "C5") (pinfunction "DGND_C5") (pintype "bidirectional"))
      (node (ref "U5") (pin "C6") (pinfunction "DGND_C6") (pintype "bidirectional"))
      (node (ref "U5") (pin "D4") (pinfunction "DGND_D4") (pintype "bidirectional"))
      (node (ref "U5") (pin "E6") (pinfunction "DGND_E6") (pintype "bidirectional"))
      (node (ref "U5") (pin "G1") (pinfunction "DGND_G1") (pintype "bidirectional"))
      (node (ref "U5") (pin "H2") (pinfunction "DGND_H2") (pintype "bidirectional"))
      (node (ref "U5") (pin "H3") (pinfunction "DGND_H3") (pintype "bidirectional"))
      (node (ref "U6") (pin "A1") (pinfunction "VSS_A1_A1") (pintype "bidirectional"))
      (node (ref "U6") (pin "A3") (pinfunction "VSSQ_A3_A3") (pintype "bidirectional"))
      (node (ref "U6") (pin "B7") (pinfunction "VSSQ_B7_B7") (pintype "bidirectional"))
      (node (ref "U6") (pin "C3") (pinfunction "VSSQ_C3_C3") (pintype "bidirectional"))
      (node (ref "U6") (pin "D7") (pinfunction "VSSQ_D7_D7") (pintype "bidirectional"))
      (node (ref "U6") (pin "E3") (pinfunction "VSS_E3_E3") (pintype "bidirectional"))
      (node (ref "U6") (pin "J1") (pinfunction "VSS_J1_J1") (pintype "bidirectional"))
      (node (ref "U7") (pin "2") (pinfunction "GND_2") (pintype "bidirectional"))
      (node (ref "U8") (pin "5") (pinfunction "GND_5") (pintype "bidirectional"))
      (node (ref "U9") (pin "GND1") (pinfunction "GND_GND1") (pintype "bidirectional"))
      (node (ref "U9") (pin "GND2") (pinfunction "GND_GND2") (pintype "bidirectional"))
      (node (ref "U9") (pin "GND3") (pinfunction "GND_GND3") (pintype "bidirectional"))
      (node (ref "U9") (pin "GND4") (pinfunction "GND_GND4") (pintype "bidirectional"))
      (node (ref "U9") (pin "VSS") (pinfunction "GND_VSS") (pintype "bidirectional"))
      (node (ref "X1") (pin "1") (pinfunction "EN__1") (pintype "input"))
      (node (ref "X1") (pin "4") (pinfunction "GND_4") (pintype "bidirectional"))
      (node (ref "X2") (pin "1") (pinfunction "EN__1") (pintype "input"))
      (node (ref "X2") (pin "4") (pinfunction "GND_4") (pintype "bidirectional"))
    )
    (net (code "11") (name "GNDPLL0") (class "Default")
      (node (ref "C26") (pin "2") (pinfunction "2_2") (pintype "bidirectional"))
      (node (ref "C27") (pin "2") (pinfunction "2_2") (pintype "bidirectional"))
      (node (ref "U4") (pin "L6") (pinfunction "GNDPLL0_L6_L6") (pintype "bidirectional"))
    )
    (net (code "12") (name "GNDPLL1") (class "Default")
      (node (ref "C23") (pin "2") (pinfunction "2_2") (pintype "bidirectional"))
      (node (ref "C24") (pin "2") (pinfunction "2_2") (pintype "bidirectional"))
      (node (ref "U4") (pin "C5") (pinfunction "GNDPLL1_C5_C5") (pintype "bidirectional"))
    )
    (net (code "13") (name "ICE_CDONE") (class "Default")
      (node (ref "R14") (pin "2") (pinfunction "2_2") (pintype "bidirectional"))
      (node (ref "TP5") (pin "X") (pinfunction "X_X") (pintype "bidirectional"))
      (node (ref "U12") (pin "C2") (pinfunction "PI7_C2_C2") (pintype "bidirectional"))
      (node (ref "U4") (pin "K8") (pinfunction "CDONE_K8_K8") (pintype "bidirectional"))
    )
    (net (code "14") (name "ICE_CRST_") (class "Default")
      (node (ref "R15") (pin "2") (pinfunction "2_2") (pintype "bidirectional"))
      (node (ref "TP7") (pin "X") (pinfunction "X_X") (pintype "bidirectional"))
      (node (ref "U12") (pin "C3") (pinfunction "PI6_C3_C3") (pintype "bidirectional"))
      (node (ref "U4") (pin "L9") (pinfunction "CRESET_B_L9_L9") (pintype "bidirectional"))
    )
    (net (code "15") (name "ICE_LED0") (class "Default")
      (node (ref "LED4") (pin "A") (pinfunction "A_A") (pintype "bidirectional"))
      (node (ref "U4") (pin "E3") (pinfunction "E3_E3") (pintype "bidirectional"))
    )
    (net (code "16") (name "ICE_LED1") (class "Default")
      (node (ref "LED3") (pin "A") (pinfunction "A_A") (pintype "bidirectional"))
      (node (ref "U4") (pin "F3") (pinfunction "F3_F3") (pintype "bidirectional"))
    )
    (net (code "17") (name "ICE_LED2") (class "Default")
      (node (ref "LED2") (pin "A") (pinfunction "A_A") (pintype "bidirectional"))
      (node (ref "U4") (pin "F4") (pinfunction "F4_F4") (pintype "bidirectional"))
    )
    (net (code "18") (name "ICE_LED3") (class "Default")
      (node (ref "LED1") (pin "A") (pinfunction "A_A") (pintype "bidirectional"))
      (node (ref "U4") (pin "G3") (pinfunction "G3_G3") (pintype "bidirectional"))
    )
    (net (code "19") (name "ICE_PIX_CLK24MHZ") (class "Default")
      (node (ref "TP6") (pin "X") (pinfunction "X_X") (pintype "bidirectional"))
      (node (ref "U4") (pin "C11") (pinfunction "C11_C11") (pintype "bidirectional"))
      (node (ref "U5") (pin "D7") (pinfunction "EXTCLK_D7") (pintype "bidirectional"))
      (node (ref "X1") (pin "2") (pinfunction "OUT_2") (pintype "bidirectional"))
    )
    (net (code "20") (name "ICE_SD_CLK") (class "Default")
      (node (ref "U4") (pin "K4") (pinfunction "K4_K4") (pintype "bidirectional"))
      (node (ref "U7") (pin "5") (pinfunction "A1_5") (pintype "bidirectional"))
      (node (ref "U8") (pin "4") (pinfunction "B0_4") (pintype "bidirectional"))
    )
    (net (code "21") (name "ICE_SD_CMD") (class "Default")
      (node (ref "R22") (pin "1") (pinfunction "1_1") (pintype "bidirectional"))
      (node (ref "U10") (pin "4") (pinfunction "B0_4") (pintype "bidirectional"))
      (node (ref "U4") (pin "L3") (pinfunction "L3_L3") (pintype "bidirectional"))
      (node (ref "U7") (pin "4") (pinfunction "A2_4") (pintype "bidirectional"))
    )
    (net (code "22") (name "ICE_SD_DAT0") (class "Default")
      (node (ref "R21") (pin "1") (pinfunction "1_1") (pintype "bidirectional"))
      (node (ref "U11") (pin "16") (pinfunction "S1A_16") (pintype "bidirectional"))
      (node (ref "U4") (pin "L2") (pinfunction "L2_L2") (pintype "bidirectional"))
    )
    (net (code "23") (name "ICE_SD_DAT1") (class "Default")
      (node (ref "R20") (pin "1") (pinfunction "1_1") (pintype "bidirectional"))
      (node (ref "U11") (pin "3") (pinfunction "S2A_3") (pintype "bidirectional"))
      (node (ref "U4") (pin "K3") (pinfunction "K3_K3") (pintype "bidirectional"))
    )
    (net (code "24") (name "ICE_SD_DAT2") (class "Default")
      (node (ref "R19") (pin "1") (pinfunction "1_1") (pintype "bidirectional"))
      (node (ref "U11") (pin "12") (pinfunction "S4A_12") (pintype "bidirectional"))
      (node (ref "U4") (pin "L5") (pinfunction "L5_L5") (pintype "bidirectional"))
    )
    (net (code "25") (name "ICE_SD_DAT3") (class "Default")
      (node (ref "R18") (pin "1") (pinfunction "1_1") (pintype "bidirectional"))
      (node (ref "U11") (pin "9") (pinfunction "S3A_9") (pintype "bidirectional"))
      (node (ref "U4") (pin "L4") (pinfunction "L4_L4") (pintype "bidirectional"))
    )
    (net (code "26") (name "ICE_SD_INIT") (class "Default")
      (node (ref "U10") (pin "6") (pinfunction "S_6") (pintype "bidirectional"))
      (node (ref "U11") (pin "15") (pinfunction "SEL_15") (pintype "bidirectional"))
      (node (ref "U4") (pin "L1") (pinfunction "L1_L1") (pintype "bidirectional"))
      (node (ref "U7") (pin "6") (pinfunction "OE_6") (pintype "bidirectional"))
      (node (ref "U8") (pin "6") (pinfunction "S_6") (pintype "bidirectional"))
    )
    (net (code "27") (name "ICE_SPI_CLK") (class "Default")
      (node (ref "TP4") (pin "X") (pinfunction "X_X") (pintype "bidirectional"))
      (node (ref "U12") (pin "M6") (pinfunction "PB2_M6_M6") (pintype "bidirectional"))
      (node (ref "U4") (pin "L10") (pinfunction "SPI_SCK_L10_L10") (pintype "bidirectional"))
    )
    (net (code "28") (name "ICE_SPI_CS_") (class "Default")
      (node (ref "TP3") (pin "X") (pinfunction "X_X") (pintype "bidirectional"))
      (node (ref "U12") (pin "B6") (pinfunction "PB6_B6_B6") (pintype "bidirectional"))
      (node (ref "U4") (pin "K10") (pinfunction "SPI_SS_B_K10_K10") (pintype "bidirectional"))
    )
    (net (code "29") (name "ICE_SPI_D0") (class "Default")
      (node (ref "TP1") (pin "X") (pinfunction "X_X") (pintype "bidirectional"))
      (node (ref "U12") (pin "F14") (pinfunction "PC9_F14_F14") (pintype "bidirectional"))
      (node (ref "U4") (pin "J9") (pinfunction "SPI_SI_J9_J9") (pintype "bidirectional"))
    )
    (net (code "30") (name "ICE_SPI_D1") (class "Default")
      (node (ref "TP2") (pin "X") (pinfunction "X_X") (pintype "bidirectional"))
      (node (ref "U12") (pin "B14") (pinfunction "PC10_B14_B14") (pintype "bidirectional"))
      (node (ref "U4") (pin "K9") (pinfunction "SPI_SO_K9_K9") (pintype "bidirectional"))
    )
    (net (code "31") (name "ICE_SPI_D2") (class "Default")
      (node (ref "U12") (pin "K1") (pinfunction "PF7_K1_K1") (pintype "bidirectional"))
      (node (ref "U4") (pin "L7") (pinfunction "L7_L7") (pintype "bidirectional"))
    )
    (net (code "32") (name "ICE_SPI_D3") (class "Default")
      (node (ref "U12") (pin "K2") (pinfunction "PF6_K2_K2") (pintype "bidirectional"))
      (node (ref "U4") (pin "K6") (pinfunction "K6_K6") (pintype "bidirectional"))
    )
    (net (code "33") (name "ICE_SPI_D4") (class "Default")
      (node (ref "U12") (pin "F4") (pinfunction "PH2_F4_F4") (pintype "bidirectional"))
      (node (ref "U4") (pin "J7") (pinfunction "J7_J7") (pintype "bidirectional"))
    )
    (net (code "34") (name "ICE_SPI_D5") (class "Default")
      (node (ref "U12") (pin "G4") (pinfunction "PH3_G4_G4") (pintype "bidirectional"))
      (node (ref "U4") (pin "K7") (pinfunction "K7_K7") (pintype "bidirectional"))
    )
    (net (code "35") (name "ICE_SPI_D6") (class "Default")
      (node (ref "U12") (pin "C10") (pinfunction "PG9_C10_C10") (pintype "bidirectional"))
      (node (ref "U4") (pin "H7") (pinfunction "H7_H7") (pintype "bidirectional"))
    )
    (net (code "36") (name "ICE_SPI_D7") (class "Default")
      (node (ref "U12") (pin "A7") (pinfunction "PG14_A7_A7") (pintype "bidirectional"))
      (node (ref "U4") (pin "L8") (pinfunction "L8_L8") (pintype "bidirectional"))
    )
    (net (code "37") (name "Net-(C10-Pad1)") (class "Default")
      (node (ref "C10") (pin "1") (pinfunction "1_1") (pintype "bidirectional"))
      (node (ref "C9") (pin "1") (pinfunction "1_1") (pintype "bidirectional"))
      (node (ref "R4") (pin "2") (pinfunction "2_2") (pintype "bidirectional"))
      (node (ref "R5") (pin "2") (pinfunction "2_2") (pintype "bidirectional"))
      (node (ref "R6") (pin "1") (pinfunction "1_1") (pintype "bidirectional"))
      (node (ref "U3") (pin "E2") (pinfunction "VOUT_E2") (pintype "bidirectional"))
      (node (ref "U3") (pin "E3") (pinfunction "VOUT_E3") (pintype "bidirectional"))
    )
    (net (code "38") (name "Net-(FB1-P$1)") (class "Default")
      (node (ref "FB1") (pin "1") (pinfunction "P$1_1") (pintype "bidirectional"))
      (node (ref "J2") (pin "VCC") (pinfunction "VCC_VCC") (pintype "bidirectional"))
      (node (ref "U13") (pin "6") (pinfunction "VBUS_6") (pintype "bidirectional"))
    )
    (net (code "39") (name "Net-(L3-Pad1)") (class "Default")
      (node (ref "L3") (pin "1") (pinfunction "1_1") (pintype "bidirectional"))
      (node (ref "U3") (pin "B2") (pinfunction "L1_B2") (pintype "bidirectional"))
      (node (ref "U3") (pin "B3") (pinfunction "L1_B3") (pintype "bidirectional"))
    )
    (net (code "40") (name "Net-(L3-Pad2)") (class "Default")
      (node (ref "L3") (pin "2") (pinfunction "2_2") (pintype "bidirectional"))
      (node (ref "U3") (pin "D2") (pinfunction "L2_D2") (pintype "bidirectional"))
      (node (ref "U3") (pin "D3") (pinfunction "L2_D3") (pintype "bidirectional"))
    )
    (net (code "41") (name "Net-(LED1-PadC)") (class "Default")
      (node (ref "LED1") (pin "C") (pinfunction "C_C") (pintype "bidirectional"))
      (node (ref "R8") (pin "1") (pinfunction "1_1") (pintype "bidirectional"))
    )
    (net (code "42") (name "Net-(LED2-PadC)") (class "Default")
      (node (ref "LED2") (pin "C") (pinfunction "C_C") (pintype "bidirectional"))
      (node (ref "R9") (pin "1") (pinfunction "1_1") (pintype "bidirectional"))
    )
    (net (code "43") (name "Net-(LED3-PadC)") (class "Default")
      (node (ref "LED3") (pin "C") (pinfunction "C_C") (pintype "bidirectional"))
      (node (ref "R10") (pin "1") (pinfunction "1_1") (pintype "bidirectional"))
    )
    (net (code "44") (name "Net-(LED4-PadC)") (class "Default")
      (node (ref "LED4") (pin "C") (pinfunction "C_C") (pintype "bidirectional"))
      (node (ref "R11") (pin "1") (pinfunction "1_1") (pintype "bidirectional"))
    )
    (net (code "45") (name "Net-(LED5-PadC)") (class "Default")
      (node (ref "LED5") (pin "C") (pinfunction "C_C") (pintype "bidirectional"))
      (node (ref "R27") (pin "1") (pinfunction "1_1") (pintype "bidirectional"))
    )
    (net (code "46") (name "Net-(LED6-PadC)") (class "Default")
      (node (ref "LED6") (pin "C") (pinfunction "C_C") (pintype "bidirectional"))
      (node (ref "R28") (pin "1") (pinfunction "1_1") (pintype "bidirectional"))
    )
    (net (code "47") (name "Net-(LED7-PadC)") (class "Default")
      (node (ref "LED7") (pin "C") (pinfunction "C_C") (pintype "bidirectional"))
      (node (ref "R29") (pin "1") (pinfunction "1_1") (pintype "bidirectional"))
    )
    (net (code "48") (name "Net-(LED8-PadC)") (class "Default")
      (node (ref "LED8") (pin "C") (pinfunction "C_C") (pintype "bidirectional"))
      (node (ref "R30") (pin "1") (pinfunction "1_1") (pintype "bidirectional"))
    )
    (net (code "49") (name "Net-(U1-SW)") (class "Default")
      (node (ref "L1") (pin "1") (pinfunction "1_1") (pintype "bidirectional"))
      (node (ref "U1") (pin "B2") (pinfunction "SW_B2") (pintype "bidirectional"))
    )
    (net (code "50") (name "Net-(U1-VOS)") (class "Default")
      (node (ref "C3") (pin "1") (pinfunction "1_1") (pintype "bidirectional"))
      (node (ref "L1") (pin "2") (pinfunction "2_2") (pintype "bidirectional"))
      (node (ref "R1") (pin "2") (pinfunction "2_2") (pintype "bidirectional"))
      (node (ref "U1") (pin "A2") (pinfunction "VOS_A2") (pintype "bidirectional"))
    )
    (net (code "51") (name "Net-(U2-SW)") (class "Default")
      (node (ref "L2") (pin "1") (pinfunction "1_1") (pintype "bidirectional"))
      (node (ref "U2") (pin "B2") (pinfunction "SW_B2") (pintype "bidirectional"))
    )
    (net (code "52") (name "Net-(U2-VOS)") (class "Default")
      (node (ref "C6") (pin "1") (pinfunction "1_1") (pintype "bidirectional"))
      (node (ref "L2") (pin "2") (pinfunction "2_2") (pintype "bidirectional"))
      (node (ref "R2") (pin "2") (pinfunction "2_2") (pintype "bidirectional"))
      (node (ref "U2") (pin "A2") (pinfunction "VOS_A2") (pintype "bidirectional"))
    )
    (net (code "53") (name "Net-(U3-FB)") (class "Default")
      (node (ref "R5") (pin "1") (pinfunction "1_1") (pintype "bidirectional"))
      (node (ref "R7") (pin "2") (pinfunction "2_2") (pintype "bidirectional"))
      (node (ref "U3") (pin "D1") (pinfunction "FB_D1") (pintype "bidirectional"))
    )
    (net (code "54") (name "Net-(U11-S1B)") (class "Default")
      (node (ref "R23") (pin "1") (pinfunction "1_1") (pintype "bidirectional"))
      (node (ref "U11") (pin "1") (pinfunction "S1B_1") (pintype "bidirectional"))
    )
    (net (code "55") (name "Net-(U11-S2B)") (class "Default")
      (node (ref "R24") (pin "1") (pinfunction "1_1") (pintype "bidirectional"))
      (node (ref "U11") (pin "4") (pinfunction "S2B_4") (pintype "bidirectional"))
    )
    (net (code "56") (name "Net-(U11-S3B)") (class "Default")
      (node (ref "R25") (pin "1") (pinfunction "1_1") (pintype "bidirectional"))
      (node (ref "U11") (pin "8") (pinfunction "S3B_8") (pintype "bidirectional"))
    )
    (net (code "57") (name "Net-(U11-S4B)") (class "Default")
      (node (ref "R26") (pin "1") (pinfunction "1_1") (pintype "bidirectional"))
      (node (ref "U11") (pin "11") (pinfunction "S4B_11") (pintype "bidirectional"))
    )
    (net (code "58") (name "Net-(U12J-OTG_HS_REXT_J15)") (class "Default")
      (node (ref "R32") (pin "2") (pinfunction "2_2") (pintype "bidirectional"))
      (node (ref "U12") (pin "J15") (pinfunction "OTG_HS_REXT_J15_J15") (pintype "bidirectional"))
    )
    (net (code "59") (name "Net-(U12J-VDD12OTGHS_J14)") (class "Default")
      (node (ref "C53") (pin "1") (pinfunction "1_1") (pintype "bidirectional"))
      (node (ref "U12") (pin "J14") (pinfunction "VDD12OTGHS_J14_J14") (pintype "bidirectional"))
    )
    (net (code "60") (name "Net-(U12K-VCAP_1_M10)") (class "Default")
      (node (ref "C70") (pin "1") (pinfunction "1_1") (pintype "bidirectional"))
      (node (ref "U12") (pin "M10") (pinfunction "VCAP_1_M10_M10") (pintype "bidirectional"))
    )
    (net (code "61") (name "Net-(U12K-VCAP_2_F13)") (class "Default")
      (node (ref "C71") (pin "1") (pinfunction "1_1") (pintype "bidirectional"))
      (node (ref "U12") (pin "F13") (pinfunction "VCAP_2_F13_F13") (pintype "bidirectional"))
    )
    (net (code "62") (name "PIX_D0") (class "Default")
      (node (ref "U4") (pin "K11") (pinfunction "K11_K11") (pintype "bidirectional"))
      (node (ref "U5") (pin "G6") (pinfunction "DOUT0_G6") (pintype "bidirectional"))
    )
    (net (code "63") (name "PIX_D1") (class "Default")
      (node (ref "U4") (pin "J10") (pinfunction "J10_J10") (pintype "bidirectional"))
      (node (ref "U5") (pin "G5") (pinfunction "DOUT1_G5") (pintype "bidirectional"))
    )
    (net (code "64") (name "PIX_D2") (class "Default")
      (node (ref "U4") (pin "J11") (pinfunction "J11_J11") (pintype "bidirectional"))
      (node (ref "U5") (pin "H4") (pinfunction "DOUT2_H4") (pintype "bidirectional"))
    )
    (net (code "65") (name "PIX_D3") (class "Default")
      (node (ref "U4") (pin "H11") (pinfunction "H11_H11") (pintype "bidirectional"))
      (node (ref "U5") (pin "G4") (pinfunction "DOUT3_G4") (pintype "bidirectional"))
    )
    (net (code "66") (name "PIX_D4") (class "Default")
      (node (ref "U4") (pin "G11") (pinfunction "G11_G11") (pintype "bidirectional"))
      (node (ref "U5") (pin "F5") (pinfunction "DOUT4_F5") (pintype "bidirectional"))
    )
    (net (code "67") (name "PIX_D5") (class "Default")
      (node (ref "U4") (pin "H10") (pinfunction "H10_H10") (pintype "bidirectional"))
      (node (ref "U5") (pin "G3") (pinfunction "DOUT5_G3") (pintype "bidirectional"))
    )
    (net (code "68") (name "PIX_D6") (class "Default")
      (node (ref "U4") (pin "G9") (pinfunction "G9_G9") (pintype "bidirectional"))
      (node (ref "U5") (pin "F4") (pinfunction "DOUT6_F4") (pintype "bidirectional"))
    )
    (net (code "69") (name "PIX_D7") (class "Default")
      (node (ref "U4") (pin "F10") (pinfunction "F10_F10") (pintype "bidirectional"))
      (node (ref "U5") (pin "E4") (pinfunction "DOUT7_E4") (pintype "bidirectional"))
    )
    (net (code "70") (name "PIX_D8") (class "Default")
      (node (ref "U4") (pin "G10") (pinfunction "G10_G10") (pintype "bidirectional"))
      (node (ref "U5") (pin "F3") (pinfunction "DOUT8_F3") (pintype "bidirectional"))
    )
    (net (code "71") (name "PIX_D9") (class "Default")
      (node (ref "U4") (pin "G8") (pinfunction "G8_G8") (pintype "bidirectional"))
      (node (ref "U5") (pin "E3") (pinfunction "DOUT9_E3") (pintype "bidirectional"))
    )
    (net (code "72") (name "PIX_D10") (class "Default")
      (node (ref "U4") (pin "F9") (pinfunction "F9_F9") (pintype "bidirectional"))
      (node (ref "U5") (pin "D3") (pinfunction "DOUT10_D3") (pintype "bidirectional"))
    )
    (net (code "73") (name "PIX_D11") (class "Default")
      (node (ref "U4") (pin "E10") (pinfunction "E10_E10") (pintype "bidirectional"))
      (node (ref "U5") (pin "E2") (pinfunction "DOUT11_E2") (pintype "bidirectional"))
    )
    (net (code "74") (name "PIX_DCLK") (class "Default")
      (node (ref "U4") (pin "F11") (pinfunction "F11_F11") (pintype "bidirectional"))
      (node (ref "U5") (pin "E1") (pinfunction "PIXCLK_E1") (pintype "bidirectional"))
    )
    (net (code "75") (name "PIX_FV") (class "Default")
      (node (ref "U4") (pin "D11") (pinfunction "D11_D11") (pintype "bidirectional"))
      (node (ref "U5") (pin "B3") (pinfunction "FRAME_VALID_B3") (pintype "bidirectional"))
    )
    (net (code "76") (name "PIX_LV") (class "Default")
      (node (ref "U4") (pin "E9") (pinfunction "E9_E9") (pintype "bidirectional"))
      (node (ref "U5") (pin "C3") (pinfunction "LINE_VALID_C3") (pintype "bidirectional"))
    )
    (net (code "77") (name "PIX_RST_") (class "Default")
      (node (ref "R16") (pin "1") (pinfunction "1_1") (pintype "bidirectional"))
      (node (ref "U4") (pin "E8") (pinfunction "E8_E8") (pintype "bidirectional"))
      (node (ref "U5") (pin "C8") (pinfunction "RST__C8") (pintype "bidirectional"))
    )
    (net (code "78") (name "PIX_SCLK") (class "Default")
      (node (ref "TP8") (pin "X") (pinfunction "X_X") (pintype "bidirectional"))
      (node (ref "U4") (pin "E11") (pinfunction "E11_E11") (pintype "bidirectional"))
      (node (ref "U5") (pin "D1") (pinfunction "SCLK_D1") (pintype "bidirectional"))
    )
    (net (code "79") (name "PIX_SDATA") (class "Default")
      (node (ref "R17") (pin "2") (pinfunction "2_2") (pintype "bidirectional"))
      (node (ref "TP9") (pin "X") (pinfunction "X_X") (pintype "bidirectional"))
      (node (ref "U4") (pin "D10") (pinfunction "D10_D10") (pintype "bidirectional"))
      (node (ref "U5") (pin "B2") (pinfunction "SDATA_B2") (pintype "bidirectional"))
    )
    (net (code "80") (name "RAM_A0") (class "Default")
      (node (ref "U4") (pin "D5") (pinfunction "D5_D5") (pintype "bidirectional"))
      (node (ref "U6") (pin "H7") (pinfunction "A0_H7") (pintype "bidirectional"))
    )
    (net (code "81") (name "RAM_A1") (class "Default")
      (node (ref "U4") (pin "A3") (pinfunction "A3_A3") (pintype "bidirectional"))
      (node (ref "U6") (pin "H8") (pinfunction "A1_H8") (pintype "bidirectional"))
    )
    (net (code "82") (name "RAM_A2") (class "Default")
      (node (ref "U4") (pin "A2") (pinfunction "A2_A2") (pintype "bidirectional"))
      (node (ref "U6") (pin "J8") (pinfunction "A2_J8") (pintype "bidirectional"))
    )
    (net (code "83") (name "RAM_A3") (class "Default")
      (node (ref "U4") (pin "A1") (pinfunction "A1_A1") (pintype "bidirectional"))
      (node (ref "U6") (pin "J7") (pinfunction "A3_J7") (pintype "bidirectional"))
    )
    (net (code "84") (name "RAM_A4") (class "Default")
      (node (ref "U4") (pin "B1") (pinfunction "B1_B1") (pintype "bidirectional"))
      (node (ref "U6") (pin "J3") (pinfunction "A4_J3") (pintype "bidirectional"))
    )
    (net (code "85") (name "RAM_A5") (class "Default")
      (node (ref "U4") (pin "C2") (pinfunction "C2_C2") (pintype "bidirectional"))
      (node (ref "U6") (pin "J2") (pinfunction "A5_J2") (pintype "bidirectional"))
    )
    (net (code "86") (name "RAM_A6") (class "Default")
      (node (ref "U4") (pin "C4") (pinfunction "C4_C4") (pintype "bidirectional"))
      (node (ref "U6") (pin "H3") (pinfunction "A6_H3") (pintype "bidirectional"))
    )
    (net (code "87") (name "RAM_A7") (class "Default")
      (node (ref "U4") (pin "D2") (pinfunction "D2_D2") (pintype "bidirectional"))
      (node (ref "U6") (pin "H2") (pinfunction "A7_H2") (pintype "bidirectional"))
    )
    (net (code "88") (name "RAM_A8") (class "Default")
      (node (ref "U4") (pin "C1") (pinfunction "C1_C1") (pintype "bidirectional"))
      (node (ref "U6") (pin "H1") (pinfunction "A8_H1") (pintype "bidirectional"))
    )
    (net (code "89") (name "RAM_A9") (class "Default")
      (node (ref "U4") (pin "C3") (pinfunction "C3_C3") (pintype "bidirectional"))
      (node (ref "U6") (pin "G3") (pinfunction "A9_G3") (pintype "bidirectional"))
    )
    (net (code "90") (name "RAM_A10") (class "Default")
      (node (ref "U4") (pin "B2") (pinfunction "B2_B2") (pintype "bidirectional"))
      (node (ref "U6") (pin "H9") (pinfunction "A10_H9") (pintype "bidirectional"))
    )
    (net (code "91") (name "RAM_A11") (class "Default")
      (node (ref "U4") (pin "E2") (pinfunction "E2_E2") (pintype "bidirectional"))
      (node (ref "U6") (pin "G2") (pinfunction "A11_G2") (pintype "bidirectional"))
    )
    (net (code "92") (name "RAM_A12") (class "Default")
      (node (ref "U4") (pin "D1") (pinfunction "D1_D1") (pintype "bidirectional"))
      (node (ref "U6") (pin "G1") (pinfunction "A12_G1") (pintype "bidirectional"))
    )
    (net (code "93") (name "RAM_BA0") (class "Default")
      (node (ref "U4") (pin "C7") (pinfunction "C7_C7") (pintype "bidirectional"))
      (node (ref "U6") (pin "G7") (pinfunction "BA0_G7") (pintype "bidirectional"))
    )
    (net (code "94") (name "RAM_BA1") (class "Default")
      (node (ref "U4") (pin "A4") (pinfunction "A4_A4") (pintype "bidirectional"))
      (node (ref "U6") (pin "G8") (pinfunction "BA1_G8") (pintype "bidirectional"))
    )
    (net (code "95") (name "RAM_CAS_") (class "Default")
      (node (ref "U4") (pin "D7") (pinfunction "D7_D7") (pintype "bidirectional"))
      (node (ref "U6") (pin "F7") (pinfunction "~{CAS}_F7") (pintype "bidirectional"))
    )
    (net (code "96") (name "RAM_CKE") (class "Default")
      (node (ref "U4") (pin "D3") (pinfunction "D3_D3") (pintype "bidirectional"))
      (node (ref "U6") (pin "F3") (pinfunction "CKE_F3") (pintype "bidirectional"))
    )
    (net (code "97") (name "RAM_CLK") (class "Default")
      (node (ref "U4") (pin "F2") (pinfunction "F2_F2") (pintype "bidirectional"))
      (node (ref "U6") (pin "F2") (pinfunction "CLK_F2") (pintype "bidirectional"))
    )
    (net (code "98") (name "RAM_CS_") (class "Default")
      (node (ref "U4") (pin "B3") (pinfunction "B3_B3") (pintype "bidirectional"))
      (node (ref "U6") (pin "G9") (pinfunction "~{CS}_G9") (pintype "bidirectional"))
    )
    (net (code "99") (name "RAM_DQ0") (class "Default")
      (node (ref "U4") (pin "B9") (pinfunction "B9_B9") (pintype "bidirectional"))
      (node (ref "U6") (pin "A8") (pinfunction "DQ0_A8") (pintype "bidirectional"))
    )
    (net (code "100") (name "RAM_DQ1") (class "Default")
      (node (ref "U4") (pin "B8") (pinfunction "B8_B8") (pintype "bidirectional"))
      (node (ref "U6") (pin "B9") (pinfunction "DQ1_B9") (pintype "bidirectional"))
    )
    (net (code "101") (name "RAM_DQ2") (class "Default")
      (node (ref "U4") (pin "A9") (pinfunction "A9_A9") (pintype "bidirectional"))
      (node (ref "U6") (pin "B8") (pinfunction "DQ2_B8") (pintype "bidirectional"))
    )
    (net (code "102") (name "RAM_DQ3") (class "Default")
      (node (ref "U4") (pin "B7") (pinfunction "B7_B7") (pintype "bidirectional"))
      (node (ref "U6") (pin "C9") (pinfunction "DQ3_C9") (pintype "bidirectional"))
    )
    (net (code "103") (name "RAM_DQ4") (class "Default")
      (node (ref "U4") (pin "A8") (pinfunction "A8_A8") (pintype "bidirectional"))
      (node (ref "U6") (pin "C8") (pinfunction "DQ4_C8") (pintype "bidirectional"))
    )
    (net (code "104") (name "RAM_DQ5") (class "Default")
      (node (ref "U4") (pin "B6") (pinfunction "B6_B6") (pintype "bidirectional"))
      (node (ref "U6") (pin "D9") (pinfunction "DQ5_D9") (pintype "bidirectional"))
    )
    (net (code "105") (name "RAM_DQ6") (class "Default")
      (node (ref "U4") (pin "A7") (pinfunction "A7_A7") (pintype "bidirectional"))
      (node (ref "U6") (pin "D8") (pinfunction "DQ6_D8") (pintype "bidirectional"))
    )
    (net (code "106") (name "RAM_DQ7") (class "Default")
      (node (ref "U4") (pin "B5") (pinfunction "B5_B5") (pintype "bidirectional"))
      (node (ref "U6") (pin "E9") (pinfunction "DQ7_E9") (pintype "bidirectional"))
    )
    (net (code "107") (name "RAM_DQ8") (class "Default")
      (node (ref "U4") (pin "F1") (pinfunction "F1_F1") (pintype "bidirectional"))
      (node (ref "U6") (pin "E1") (pinfunction "DQ8_E1") (pintype "bidirectional"))
    )
    (net (code "108") (name "RAM_DQ9") (class "Default")
      (node (ref "U4") (pin "G1") (pinfunction "G1_G1") (pintype "bidirectional"))
      (node (ref "U6") (pin "D2") (pinfunction "DQ9_D2") (pintype "bidirectional"))
    )
    (net (code "109") (name "RAM_DQ10") (class "Default")
      (node (ref "U4") (pin "G2") (pinfunction "G2_G2") (pintype "bidirectional"))
      (node (ref "U6") (pin "D1") (pinfunction "DQ10_D1") (pintype "bidirectional"))
    )
    (net (code "110") (name "RAM_DQ11") (class "Default")
      (node (ref "U4") (pin "H1") (pinfunction "H1_H1") (pintype "bidirectional"))
      (node (ref "U6") (pin "C2") (pinfunction "DQ11_C2") (pintype "bidirectional"))
    )
    (net (code "111") (name "RAM_DQ12") (class "Default")
      (node (ref "U4") (pin "H2") (pinfunction "H2_H2") (pintype "bidirectional"))
      (node (ref "U6") (pin "C1") (pinfunction "DQ12_C1") (pintype "bidirectional"))
    )
    (net (code "112") (name "RAM_DQ13") (class "Default")
      (node (ref "U4") (pin "J1") (pinfunction "J1_J1") (pintype "bidirectional"))
      (node (ref "U6") (pin "B2") (pinfunction "DQ13_B2") (pintype "bidirectional"))
    )
    (net (code "113") (name "RAM_DQ14") (class "Default")
      (node (ref "U4") (pin "J2") (pinfunction "J2_J2") (pintype "bidirectional"))
      (node (ref "U6") (pin "B1") (pinfunction "DQ14_B1") (pintype "bidirectional"))
    )
    (net (code "114") (name "RAM_DQ15") (class "Default")
      (node (ref "U4") (pin "K2") (pinfunction "K2_K2") (pintype "bidirectional"))
      (node (ref "U6") (pin "A2") (pinfunction "DQ15_A2") (pintype "bidirectional"))
    )
    (net (code "115") (name "RAM_DQM0") (class "Default")
      (node (ref "U4") (pin "A6") (pinfunction "A6_A6") (pintype "bidirectional"))
      (node (ref "U6") (pin "E8") (pinfunction "LDQM_E8") (pintype "bidirectional"))
    )
    (net (code "116") (name "RAM_DQM1") (class "Default")
      (node (ref "U4") (pin "E1") (pinfunction "E1_E1") (pintype "bidirectional"))
      (node (ref "U6") (pin "F1") (pinfunction "UDQM_F1") (pintype "bidirectional"))
    )
    (net (code "117") (name "RAM_RAS_") (class "Default")
      (node (ref "U4") (pin "A5") (pinfunction "A5_A5") (pintype "bidirectional"))
      (node (ref "U6") (pin "F8") (pinfunction "~{RAS}_F8") (pintype "bidirectional"))
    )
    (net (code "118") (name "RAM_WE_") (class "Default")
      (node (ref "U4") (pin "B4") (pinfunction "B4_B4") (pintype "bidirectional"))
      (node (ref "U6") (pin "F9") (pinfunction "~{WE}_F9") (pintype "bidirectional"))
    )
    (net (code "119") (name "SD_CLK") (class "Default")
      (node (ref "U7") (pin "8") (pinfunction "B1_8") (pintype "bidirectional"))
      (node (ref "U8") (pin "3") (pinfunction "A_3") (pintype "bidirectional"))
      (node (ref "U9") (pin "CLK") (pinfunction "CLK_CLK") (pintype "bidirectional"))
    )
    (net (code "120") (name "SD_CMD") (class "Default")
      (node (ref "U10") (pin "3") (pinfunction "A_3") (pintype "bidirectional"))
      (node (ref "U7") (pin "1") (pinfunction "B2_1") (pintype "bidirectional"))
      (node (ref "U9") (pin "CMD") (pinfunction "CMD_CMD") (pintype "bidirectional"))
    )
    (net (code "121") (name "SD_DAT0") (class "Default")
      (node (ref "U11") (pin "5") (pinfunction "D2_5") (pintype "bidirectional"))
      (node (ref "U9") (pin "DAT0") (pinfunction "DAT0_DAT0") (pintype "bidirectional"))
    )
    (net (code "122") (name "SD_DAT1") (class "Default")
      (node (ref "U11") (pin "2") (pinfunction "D1_2") (pintype "bidirectional"))
      (node (ref "U9") (pin "DAT1") (pinfunction "DAT1_DAT1") (pintype "bidirectional"))
    )
    (net (code "123") (name "SD_DAT2") (class "Default")
      (node (ref "U11") (pin "10") (pinfunction "D4_10") (pintype "bidirectional"))
      (node (ref "U9") (pin "DAT2") (pinfunction "DAT2_DAT2") (pintype "bidirectional"))
    )
    (net (code "124") (name "SD_DAT3") (class "Default")
      (node (ref "U11") (pin "7") (pinfunction "D3_7") (pintype "bidirectional"))
      (node (ref "U9") (pin "DAT3") (pinfunction "DAT3_DAT3") (pintype "bidirectional"))
    )
    (net (code "125") (name "STM_BOOT") (class "Default")
      (node (ref "H1") (pin "8") (pinfunction "8_8") (pintype "bidirectional"))
      (node (ref "R31") (pin "2") (pinfunction "2_2") (pintype "bidirectional"))
      (node (ref "U12") (pin "D6") (pinfunction "BOOT0_D6_D6") (pintype "bidirectional"))
    )
    (net (code "126") (name "STM_CLK24MHZ") (class "Default")
      (node (ref "TP10") (pin "X") (pinfunction "X_X") (pintype "bidirectional"))
      (node (ref "U12") (pin "G1") (pinfunction "PH0_G1_G1") (pintype "bidirectional"))
      (node (ref "X2") (pin "2") (pinfunction "OUT_2") (pintype "bidirectional"))
    )
    (net (code "127") (name "STM_LED0") (class "Default")
      (node (ref "LED8") (pin "A") (pinfunction "A_A") (pintype "bidirectional"))
      (node (ref "U12") (pin "R10") (pinfunction "PE12_R10_R10") (pintype "bidirectional"))
    )
    (net (code "128") (name "STM_LED1") (class "Default")
      (node (ref "LED7") (pin "A") (pinfunction "A_A") (pintype "bidirectional"))
      (node (ref "U12") (pin "R11") (pinfunction "PE15_R11_R11") (pintype "bidirectional"))
    )
    (net (code "129") (name "STM_LED2") (class "Default")
      (node (ref "LED6") (pin "A") (pinfunction "A_A") (pintype "bidirectional"))
      (node (ref "U12") (pin "R12") (pinfunction "PB10_R12_R12") (pintype "bidirectional"))
    )
    (net (code "130") (name "STM_LED3") (class "Default")
      (node (ref "LED5") (pin "A") (pinfunction "A_A") (pintype "bidirectional"))
      (node (ref "U12") (pin "R13") (pinfunction "PB11_R13_R13") (pintype "bidirectional"))
    )
    (net (code "131") (name "STM_RST_") (class "Default")
      (node (ref "C52") (pin "1") (pinfunction "1_1") (pintype "bidirectional"))
      (node (ref "H1") (pin "7") (pinfunction "7_7") (pintype "bidirectional"))
      (node (ref "U12") (pin "J1") (pinfunction "NRST_J1_J1") (pintype "bidirectional"))
    )
    (net (code "132") (name "STM_SWCLK") (class "Default")
      (node (ref "H1") (pin "2") (pinfunction "2_2") (pintype "bidirectional"))
      (node (ref "U12") (pin "A14") (pinfunction "PA14_A14_A14") (pintype "bidirectional"))
    )
    (net (code "133") (name "STM_SWDIO") (class "Default")
      (node (ref "H1") (pin "1") (pinfunction "1_1") (pintype "bidirectional"))
      (node (ref "U12") (pin "A15") (pinfunction "PA13_A15_A15") (pintype "bidirectional"))
    )
    (net (code "134") (name "USB_D+") (class "Default")
      (node (ref "J2") (pin "D+") (pinfunction "D+_D+") (pintype "bidirectional"))
      (node (ref "U12") (pin "R15") (pinfunction "PB15_R15_R15") (pintype "bidirectional"))
      (node (ref "U13") (pin "1") (pinfunction "D+_1") (pintype "bidirectional"))
    )
    (net (code "135") (name "USB_D-") (class "Default")
      (node (ref "J2") (pin "D-") (pinfunction "D-_D-") (pintype "bidirectional"))
      (node (ref "U12") (pin "R14") (pinfunction "PB14_R14_R14") (pintype "bidirectional"))
      (node (ref "U13") (pin "2") (pinfunction "D-_2") (pintype "bidirectional"))
    )
    (net (code "136") (name "VCCPLL0") (class "Default")
      (node (ref "C26") (pin "1") (pinfunction "1_1") (pintype "bidirectional"))
      (node (ref "C27") (pin "1") (pinfunction "1_1") (pintype "bidirectional"))
      (node (ref "R13") (pin "1") (pinfunction "1_1") (pintype "bidirectional"))
      (node (ref "U4") (pin "J6") (pinfunction "VCCPLL0_J6_J6") (pintype "bidirectional"))
    )
    (net (code "137") (name "VCCPLL1") (class "Default")
      (node (ref "C23") (pin "1") (pinfunction "1_1") (pintype "bidirectional"))
      (node (ref "C24") (pin "1") (pinfunction "1_1") (pintype "bidirectional"))
      (node (ref "R12") (pin "1") (pinfunction "1_1") (pintype "bidirectional"))
      (node (ref "U4") (pin "C6") (pinfunction "VCCPLL1_C6_C6") (pintype "bidirectional"))
    )
    (net (code "138") (name "VDD") (class "Default")
      (node (ref "C1") (pin "1") (pinfunction "1_1") (pintype "bidirectional"))
      (node (ref "C2") (pin "1") (pinfunction "1_1") (pintype "bidirectional"))
      (node (ref "C4") (pin "1") (pinfunction "1_1") (pintype "bidirectional"))
      (node (ref "C5") (pin "1") (pinfunction "1_1") (pintype "bidirectional"))
      (node (ref "C7") (pin "1") (pinfunction "1_1") (pintype "bidirectional"))
      (node (ref "C8") (pin "1") (pinfunction "1_1") (pintype "bidirectional"))
      (node (ref "R3") (pin "1") (pinfunction "1_1") (pintype "bidirectional"))
      (node (ref "U1") (pin "B1") (pinfunction "VIN_B1") (pintype "bidirectional"))
      (node (ref "U1") (pin "C2") (pinfunction "EN_C2") (pintype "bidirectional"))
      (node (ref "U2") (pin "B1") (pinfunction "VIN_B1") (pintype "bidirectional"))
      (node (ref "U3") (pin "A1") (pinfunction "EN_A1") (pintype "bidirectional"))
      (node (ref "U3") (pin "A2") (pinfunction "VIN_A2") (pintype "bidirectional"))
      (node (ref "U3") (pin "A3") (pinfunction "VIN_A3") (pintype "bidirectional"))
    )
    (net (code "139") (name "VDDIN") (class "Default")
      (node (ref "FB1") (pin "2") (pinfunction "P$2_2") (pintype "bidirectional"))
      (node (ref "H1") (pin "9") (pinfunction "9_9") (pintype "bidirectional"))
      (node (ref "R3") (pin "2") (pinfunction "2_2") (pintype "bidirectional"))
    )
    (net (code "140") (name "unconnected-(H1-Pad3)") (class "Default")
      (node (ref "H1") (pin "3") (pinfunction "3_3") (pintype "bidirectional"))
    )
    (net (code "141") (name "unconnected-(H1-Pad4)") (class "Default")
      (node (ref "H1") (pin "4") (pinfunction "4_4") (pintype "bidirectional"))
    )
    (net (code "142") (name "unconnected-(H1-Pad5)") (class "Default")
      (node (ref "H1") (pin "5") (pinfunction "5_5") (pintype "bidirectional"))
    )
    (net (code "143") (name "unconnected-(H1-Pad6)") (class "Default")
      (node (ref "H1") (pin "6") (pinfunction "6_6") (pintype "bidirectional"))
    )
    (net (code "144") (name "unconnected-(J2-PadID)") (class "Default")
      (node (ref "J2") (pin "ID") (pinfunction "ID_ID") (pintype "bidirectional"))
    )
    (net (code "145") (name "unconnected-(U4-PadA10)") (class "Default")
      (node (ref "U4") (pin "A10") (pinfunction "A10_A10") (pintype "bidirectional"))
    )
    (net (code "146") (name "unconnected-(U4-PadA11)") (class "Default")
      (node (ref "U4") (pin "A11") (pinfunction "A11_A11") (pintype "bidirectional"))
    )
    (net (code "147") (name "unconnected-(U4-PadB11)") (class "Default")
      (node (ref "U4") (pin "B11") (pinfunction "B11_B11") (pintype "bidirectional"))
    )
    (net (code "148") (name "unconnected-(U4-PadC8)") (class "Default")
      (node (ref "U4") (pin "C8") (pinfunction "C8_C8") (pintype "bidirectional"))
    )
    (net (code "149") (name "unconnected-(U4-PadC9)") (class "Default")
      (node (ref "U4") (pin "C9") (pinfunction "C9_C9") (pintype "bidirectional"))
    )
    (net (code "150") (name "unconnected-(U4-PadD9)") (class "Default")
      (node (ref "U4") (pin "D9") (pinfunction "D9_D9") (pintype "bidirectional"))
    )
    (net (code "151") (name "unconnected-(U4-PadH3)") (class "Default")
      (node (ref "U4") (pin "H3") (pinfunction "H3_H3") (pintype "bidirectional"))
    )
    (net (code "152") (name "unconnected-(U4-PadH9)") (class "Default")
      (node (ref "U4") (pin "H9") (pinfunction "H9_H9") (pintype "bidirectional"))
    )
    (net (code "153") (name "unconnected-(U4-PadJ3)") (class "Default")
      (node (ref "U4") (pin "J3") (pinfunction "J3_J3") (pintype "bidirectional"))
    )
    (net (code "154") (name "unconnected-(U4-PadJ4)") (class "Default")
      (node (ref "U4") (pin "J4") (pinfunction "J4_J4") (pintype "bidirectional"))
    )
    (net (code "155") (name "unconnected-(U4-PadJ5)") (class "Default")
      (node (ref "U4") (pin "J5") (pinfunction "J5_J5") (pintype "bidirectional"))
    )
    (net (code "156") (name "unconnected-(U4-PadJ8)") (class "Default")
      (node (ref "U4") (pin "J8") (pinfunction "J8_J8") (pintype "bidirectional"))
    )
    (net (code "157") (name "unconnected-(U4-PadK1)") (class "Default")
      (node (ref "U4") (pin "K1") (pinfunction "K1_K1") (pintype "bidirectional"))
    )
    (net (code "158") (name "unconnected-(U4-PadK5)") (class "Default")
      (node (ref "U4") (pin "K5") (pinfunction "K5_K5") (pintype "bidirectional"))
    )
    (net (code "159") (name "unconnected-(U4E-VPP_FAST_B10-PadB10)") (class "Default")
      (node (ref "U4") (pin "B10") (pinfunction "VPP_FAST_B10_B10") (pintype "bidirectional"))
    )
    (net (code "160") (name "unconnected-(U5A-VAAHV_NPIX-PadA2)") (class "Default")
      (node (ref "U5") (pin "A2") (pinfunction "VAAHV_NPIX_A2") (pintype "bidirectional"))
    )
    (net (code "161") (name "unconnected-(U5B-CLK_N-PadE7)") (class "Default")
      (node (ref "U5") (pin "E7") (pinfunction "CLK_N_E7") (pintype "bidirectional"))
    )
    (net (code "162") (name "unconnected-(U5B-CLK_P-PadF7)") (class "Default")
      (node (ref "U5") (pin "F7") (pinfunction "CLK_P_F7") (pintype "bidirectional"))
    )
    (net (code "163") (name "unconnected-(U5B-DATA2_N-PadG7)") (class "Default")
      (node (ref "U5") (pin "G7") (pinfunction "DATA2_N_G7") (pintype "bidirectional"))
    )
    (net (code "164") (name "unconnected-(U5B-DATA2_P-PadH7)") (class "Default")
      (node (ref "U5") (pin "H7") (pinfunction "DATA2_P_H7") (pintype "bidirectional"))
    )
    (net (code "165") (name "unconnected-(U5B-DATA_N-PadD8)") (class "Default")
      (node (ref "U5") (pin "D8") (pinfunction "DATA_N_D8") (pintype "bidirectional"))
    )
    (net (code "166") (name "unconnected-(U5B-DATA_P-PadE8)") (class "Default")
      (node (ref "U5") (pin "E8") (pinfunction "DATA_P_E8") (pintype "bidirectional"))
    )
    (net (code "167") (name "unconnected-(U5B-FLASH-PadC2)") (class "Default")
      (node (ref "U5") (pin "C2") (pinfunction "FLASH_C2") (pintype "bidirectional"))
    )
    (net (code "168") (name "unconnected-(U5B-SHUTTER-PadB8)") (class "Default")
      (node (ref "U5") (pin "B8") (pinfunction "SHUTTER_B8") (pintype "bidirectional"))
    )
    (net (code "169") (name "unconnected-(U5B-TRIGGER-PadC7)") (class "Default")
      (node (ref "U5") (pin "C7") (pinfunction "TRIGGER_C7") (pintype "bidirectional"))
    )
    (net (code "170") (name "unconnected-(U6B-NC-PadE2)") (class "Default")
      (node (ref "U6") (pin "E2") (pinfunction "NC_E2") (pintype "bidirectional"))
    )
    (net (code "171") (name "unconnected-(U8-B1-Pad2)") (class "Default")
      (node (ref "U8") (pin "2") (pinfunction "B1_2") (pintype "bidirectional"))
    )
    (net (code "172") (name "unconnected-(U9-PadDET)") (class "Default")
      (node (ref "U9") (pin "DET") (pinfunction "DET_DET") (pintype "bidirectional"))
    )
    (net (code "173") (name "unconnected-(U10-B1-Pad2)") (class "Default")
      (node (ref "U10") (pin "2") (pinfunction "B1_2") (pintype "bidirectional"))
    )
    (net (code "174") (name "unconnected-(U12A-PA0_N3-PadN3)") (class "Default")
      (node (ref "U12") (pin "N3") (pinfunction "PA0_N3_N3") (pintype "bidirectional"))
    )
    (net (code "175") (name "unconnected-(U12A-PA1_N2-PadN2)") (class "Default")
      (node (ref "U12") (pin "N2") (pinfunction "PA1_N2_N2") (pintype "bidirectional"))
    )
    (net (code "176") (name "unconnected-(U12A-PA2_P2-PadP2)") (class "Default")
      (node (ref "U12") (pin "P2") (pinfunction "PA2_P2_P2") (pintype "bidirectional"))
    )
    (net (code "177") (name "unconnected-(U12A-PA3_R2-PadR2)") (class "Default")
      (node (ref "U12") (pin "R2") (pinfunction "PA3_R2_R2") (pintype "bidirectional"))
    )
    (net (code "178") (name "unconnected-(U12A-PA4_N4-PadN4)") (class "Default")
      (node (ref "U12") (pin "N4") (pinfunction "PA4_N4_N4") (pintype "bidirectional"))
    )
    (net (code "179") (name "unconnected-(U12A-PA5_P4-PadP4)") (class "Default")
      (node (ref "U12") (pin "P4") (pinfunction "PA5_P4_P4") (pintype "bidirectional"))
    )
    (net (code "180") (name "unconnected-(U12A-PA6_P3-PadP3)") (class "Default")
      (node (ref "U12") (pin "P3") (pinfunction "PA6_P3_P3") (pintype "bidirectional"))
    )
    (net (code "181") (name "unconnected-(U12A-PA7_R3-PadR3)") (class "Default")
      (node (ref "U12") (pin "R3") (pinfunction "PA7_R3_R3") (pintype "bidirectional"))
    )
    (net (code "182") (name "unconnected-(U12A-PA8_F15-PadF15)") (class "Default")
      (node (ref "U12") (pin "F15") (pinfunction "PA8_F15_F15") (pintype "bidirectional"))
    )
    (net (code "183") (name "unconnected-(U12A-PA9_E15-PadE15)") (class "Default")
      (node (ref "U12") (pin "E15") (pinfunction "PA9_E15_E15") (pintype "bidirectional"))
    )
    (net (code "184") (name "unconnected-(U12A-PA10_D15-PadD15)") (class "Default")
      (node (ref "U12") (pin "D15") (pinfunction "PA10_D15_D15") (pintype "bidirectional"))
    )
    (net (code "185") (name "unconnected-(U12A-PA11_C15-PadC15)") (class "Default")
      (node (ref "U12") (pin "C15") (pinfunction "PA11_C15_C15") (pintype "bidirectional"))
    )
    (net (code "186") (name "unconnected-(U12A-PA12_B15-PadB15)") (class "Default")
      (node (ref "U12") (pin "B15") (pinfunction "PA12_B15_B15") (pintype "bidirectional"))
    )
    (net (code "187") (name "unconnected-(U12A-PA15_A13-PadA13)") (class "Default")
      (node (ref "U12") (pin "A13") (pinfunction "PA15_A13_A13") (pintype "bidirectional"))
    )
    (net (code "188") (name "unconnected-(U12B-PB0_R5-PadR5)") (class "Default")
      (node (ref "U12") (pin "R5") (pinfunction "PB0_R5_R5") (pintype "bidirectional"))
    )
    (net (code "189") (name "unconnected-(U12B-PB1_R4-PadR4)") (class "Default")
      (node (ref "U12") (pin "R4") (pinfunction "PB1_R4_R4") (pintype "bidirectional"))
    )
    (net (code "190") (name "unconnected-(U12B-PB3_A10-PadA10)") (class "Default")
      (node (ref "U12") (pin "A10") (pinfunction "PB3_A10_A10") (pintype "bidirectional"))
    )
    (net (code "191") (name "unconnected-(U12B-PB4_A9-PadA9)") (class "Default")
      (node (ref "U12") (pin "A9") (pinfunction "PB4_A9_A9") (pintype "bidirectional"))
    )
    (net (code "192") (name "unconnected-(U12B-PB5_A6-PadA6)") (class "Default")
      (node (ref "U12") (pin "A6") (pinfunction "PB5_A6_A6") (pintype "bidirectional"))
    )
    (net (code "193") (name "unconnected-(U12B-PB7_B5-PadB5)") (class "Default")
      (node (ref "U12") (pin "B5") (pinfunction "PB7_B5_B5") (pintype "bidirectional"))
    )
    (net (code "194") (name "unconnected-(U12B-PB8_A5-PadA5)") (class "Default")
      (node (ref "U12") (pin "A5") (pinfunction "PB8_A5_A5") (pintype "bidirectional"))
    )
    (net (code "195") (name "unconnected-(U12B-PB9_B4-PadB4)") (class "Default")
      (node (ref "U12") (pin "B4") (pinfunction "PB9_B4_B4") (pintype "bidirectional"))
    )
    (net (code "196") (name "unconnected-(U12B-PB12_P12-PadP12)") (class "Default")
      (node (ref "U12") (pin "P12") (pinfunction "PB12_P12_P12") (pintype "bidirectional"))
    )
    (net (code "197") (name "unconnected-(U12B-PB13_P13-PadP13)") (class "Default")
      (node (ref "U12") (pin "P13") (pinfunction "PB13_P13_P13") (pintype "bidirectional"))
    )
    (net (code "198") (name "unconnected-(U12C-PC0_M2-PadM2)") (class "Default")
      (node (ref "U12") (pin "M2") (pinfunction "PC0_M2_M2") (pintype "bidirectional"))
    )
    (net (code "199") (name "unconnected-(U12C-PC1_M3-PadM3)") (class "Default")
      (node (ref "U12") (pin "M3") (pinfunction "PC1_M3_M3") (pintype "bidirectional"))
    )
    (net (code "200") (name "unconnected-(U12C-PC2_M4-PadM4)") (class "Default")
      (node (ref "U12") (pin "M4") (pinfunction "PC2_M4_M4") (pintype "bidirectional"))
    )
    (net (code "201") (name "unconnected-(U12C-PC3_M5-PadM5)") (class "Default")
      (node (ref "U12") (pin "M5") (pinfunction "PC3_M5_M5") (pintype "bidirectional"))
    )
    (net (code "202") (name "unconnected-(U12C-PC4_N5-PadN5)") (class "Default")
      (node (ref "U12") (pin "N5") (pinfunction "PC4_N5_N5") (pintype "bidirectional"))
    )
    (net (code "203") (name "unconnected-(U12C-PC5_P5-PadP5)") (class "Default")
      (node (ref "U12") (pin "P5") (pinfunction "PC5_P5_P5") (pintype "bidirectional"))
    )
    (net (code "204") (name "unconnected-(U12C-PC6_H15-PadH15)") (class "Default")
      (node (ref "U12") (pin "H15") (pinfunction "PC6_H15_H15") (pintype "bidirectional"))
    )
    (net (code "205") (name "unconnected-(U12C-PC7_G15-PadG15)") (class "Default")
      (node (ref "U12") (pin "G15") (pinfunction "PC7_G15_G15") (pintype "bidirectional"))
    )
    (net (code "206") (name "unconnected-(U12C-PC8_G14-PadG14)") (class "Default")
      (node (ref "U12") (pin "G14") (pinfunction "PC8_G14_G14") (pintype "bidirectional"))
    )
    (net (code "207") (name "unconnected-(U12C-PC11_B13-PadB13)") (class "Default")
      (node (ref "U12") (pin "B13") (pinfunction "PC11_B13_B13") (pintype "bidirectional"))
    )
    (net (code "208") (name "unconnected-(U12C-PC12_A12-PadA12)") (class "Default")
      (node (ref "U12") (pin "A12") (pinfunction "PC12_A12_A12") (pintype "bidirectional"))
    )
    (net (code "209") (name "unconnected-(U12C-PC13_D1-PadD1)") (class "Default")
      (node (ref "U12") (pin "D1") (pinfunction "PC13_D1_D1") (pintype "bidirectional"))
    )
    (net (code "210") (name "unconnected-(U12C-PC14_E1-PadE1)") (class "Default")
      (node (ref "U12") (pin "E1") (pinfunction "PC14_E1_E1") (pintype "bidirectional"))
    )
    (net (code "211") (name "unconnected-(U12C-PC15_F1-PadF1)") (class "Default")
      (node (ref "U12") (pin "F1") (pinfunction "PC15_F1_F1") (pintype "bidirectional"))
    )
    (net (code "212") (name "unconnected-(U12D-PD0_B12-PadB12)") (class "Default")
      (node (ref "U12") (pin "B12") (pinfunction "PD0_B12_B12") (pintype "bidirectional"))
    )
    (net (code "213") (name "unconnected-(U12D-PD1_C12-PadC12)") (class "Default")
      (node (ref "U12") (pin "C12") (pinfunction "PD1_C12_C12") (pintype "bidirectional"))
    )
    (net (code "214") (name "unconnected-(U12D-PD2_D12-PadD12)") (class "Default")
      (node (ref "U12") (pin "D12") (pinfunction "PD2_D12_D12") (pintype "bidirectional"))
    )
    (net (code "215") (name "unconnected-(U12D-PD3_D11-PadD11)") (class "Default")
      (node (ref "U12") (pin "D11") (pinfunction "PD3_D11_D11") (pintype "bidirectional"))
    )
    (net (code "216") (name "unconnected-(U12D-PD4_D10-PadD10)") (class "Default")
      (node (ref "U12") (pin "D10") (pinfunction "PD4_D10_D10") (pintype "bidirectional"))
    )
    (net (code "217") (name "unconnected-(U12D-PD5_C11-PadC11)") (class "Default")
      (node (ref "U12") (pin "C11") (pinfunction "PD5_C11_C11") (pintype "bidirectional"))
    )
    (net (code "218") (name "unconnected-(U12D-PD6_B11-PadB11)") (class "Default")
      (node (ref "U12") (pin "B11") (pinfunction "PD6_B11_B11") (pintype "bidirectional"))
    )
    (net (code "219") (name "unconnected-(U12D-PD7_A11-PadA11)") (class "Default")
      (node (ref "U12") (pin "A11") (pinfunction "PD7_A11_A11") (pintype "bidirectional"))
    )
    (net (code "220") (name "unconnected-(U12D-PD8_P15-PadP15)") (class "Default")
      (node (ref "U12") (pin "P15") (pinfunction "PD8_P15_P15") (pintype "bidirectional"))
    )
    (net (code "221") (name "unconnected-(U12D-PD9_P14-PadP14)") (class "Default")
      (node (ref "U12") (pin "P14") (pinfunction "PD9_P14_P14") (pintype "bidirectional"))
    )
    (net (code "222") (name "unconnected-(U12D-PD10_N15-PadN15)") (class "Default")
      (node (ref "U12") (pin "N15") (pinfunction "PD10_N15_N15") (pintype "bidirectional"))
    )
    (net (code "223") (name "unconnected-(U12D-PD11_N14-PadN14)") (class "Default")
      (node (ref "U12") (pin "N14") (pinfunction "PD11_N14_N14") (pintype "bidirectional"))
    )
    (net (code "224") (name "unconnected-(U12D-PD12_N13-PadN13)") (class "Default")
      (node (ref "U12") (pin "N13") (pinfunction "PD12_N13_N13") (pintype "bidirectional"))
    )
    (net (code "225") (name "unconnected-(U12D-PD13_M15-PadM15)") (class "Default")
      (node (ref "U12") (pin "M15") (pinfunction "PD13_M15_M15") (pintype "bidirectional"))
    )
    (net (code "226") (name "unconnected-(U12D-PD14_M14-PadM14)") (class "Default")
      (node (ref "U12") (pin "M14") (pinfunction "PD14_M14_M14") (pintype "bidirectional"))
    )
    (net (code "227") (name "unconnected-(U12D-PD15_L14-PadL14)") (class "Default")
      (node (ref "U12") (pin "L14") (pinfunction "PD15_L14_L14") (pintype "bidirectional"))
    )
    (net (code "228") (name "unconnected-(U12E-PE0_A4-PadA4)") (class "Default")
      (node (ref "U12") (pin "A4") (pinfunction "PE0_A4_A4") (pintype "bidirectional"))
    )
    (net (code "229") (name "unconnected-(U12E-PE1_A3-PadA3)") (class "Default")
      (node (ref "U12") (pin "A3") (pinfunction "PE1_A3_A3") (pintype "bidirectional"))
    )
    (net (code "230") (name "unconnected-(U12E-PE2_A2-PadA2)") (class "Default")
      (node (ref "U12") (pin "A2") (pinfunction "PE2_A2_A2") (pintype "bidirectional"))
    )
    (net (code "231") (name "unconnected-(U12E-PE3_A1-PadA1)") (class "Default")
      (node (ref "U12") (pin "A1") (pinfunction "PE3_A1_A1") (pintype "bidirectional"))
    )
    (net (code "232") (name "unconnected-(U12E-PE4_B1-PadB1)") (class "Default")
      (node (ref "U12") (pin "B1") (pinfunction "PE4_B1_B1") (pintype "bidirectional"))
    )
    (net (code "233") (name "unconnected-(U12E-PE5_B2-PadB2)") (class "Default")
      (node (ref "U12") (pin "B2") (pinfunction "PE5_B2_B2") (pintype "bidirectional"))
    )
    (net (code "234") (name "unconnected-(U12E-PE6_B3-PadB3)") (class "Default")
      (node (ref "U12") (pin "B3") (pinfunction "PE6_B3_B3") (pintype "bidirectional"))
    )
    (net (code "235") (name "unconnected-(U12E-PE7_R8-PadR8)") (class "Default")
      (node (ref "U12") (pin "R8") (pinfunction "PE7_R8_R8") (pintype "bidirectional"))
    )
    (net (code "236") (name "unconnected-(U12E-PE8_P8-PadP8)") (class "Default")
      (node (ref "U12") (pin "P8") (pinfunction "PE8_P8_P8") (pintype "bidirectional"))
    )
    (net (code "237") (name "unconnected-(U12E-PE9_P9-PadP9)") (class "Default")
      (node (ref "U12") (pin "P9") (pinfunction "PE9_P9_P9") (pintype "bidirectional"))
    )
    (net (code "238") (name "unconnected-(U12E-PE10_R9-PadR9)") (class "Default")
      (node (ref "U12") (pin "R9") (pinfunction "PE10_R9_R9") (pintype "bidirectional"))
    )
    (net (code "239") (name "unconnected-(U12E-PE11_P10-PadP10)") (class "Default")
      (node (ref "U12") (pin "P10") (pinfunction "PE11_P10_P10") (pintype "bidirectional"))
    )
    (net (code "240") (name "unconnected-(U12E-PE13_N11-PadN11)") (class "Default")
      (node (ref "U12") (pin "N11") (pinfunction "PE13_N11_N11") (pintype "bidirectional"))
    )
    (net (code "241") (name "unconnected-(U12E-PE14_P11-PadP11)") (class "Default")
      (node (ref "U12") (pin "P11") (pinfunction "PE14_P11_P11") (pintype "bidirectional"))
    )
    (net (code "242") (name "unconnected-(U12F-PF0_E2-PadE2)") (class "Default")
      (node (ref "U12") (pin "E2") (pinfunction "PF0_E2_E2") (pintype "bidirectional"))
    )
    (net (code "243") (name "unconnected-(U12F-PF1_H3-PadH3)") (class "Default")
      (node (ref "U12") (pin "H3") (pinfunction "PF1_H3_H3") (pintype "bidirectional"))
    )
    (net (code "244") (name "unconnected-(U12F-PF2_H2-PadH2)") (class "Default")
      (node (ref "U12") (pin "H2") (pinfunction "PF2_H2_H2") (pintype "bidirectional"))
    )
    (net (code "245") (name "unconnected-(U12F-PF3_J2-PadJ2)") (class "Default")
      (node (ref "U12") (pin "J2") (pinfunction "PF3_J2_J2") (pintype "bidirectional"))
    )
    (net (code "246") (name "unconnected-(U12F-PF4_J3-PadJ3)") (class "Default")
      (node (ref "U12") (pin "J3") (pinfunction "PF4_J3_J3") (pintype "bidirectional"))
    )
    (net (code "247") (name "unconnected-(U12F-PF5_K3-PadK3)") (class "Default")
      (node (ref "U12") (pin "K3") (pinfunction "PF5_K3_K3") (pintype "bidirectional"))
    )
    (net (code "248") (name "unconnected-(U12F-PF8_L3-PadL3)") (class "Default")
      (node (ref "U12") (pin "L3") (pinfunction "PF8_L3_L3") (pintype "bidirectional"))
    )
    (net (code "249") (name "unconnected-(U12F-PF9_L2-PadL2)") (class "Default")
      (node (ref "U12") (pin "L2") (pinfunction "PF9_L2_L2") (pintype "bidirectional"))
    )
    (net (code "250") (name "unconnected-(U12F-PF10_L1-PadL1)") (class "Default")
      (node (ref "U12") (pin "L1") (pinfunction "PF10_L1_L1") (pintype "bidirectional"))
    )
    (net (code "251") (name "unconnected-(U12F-PF11_R6-PadR6)") (class "Default")
      (node (ref "U12") (pin "R6") (pinfunction "PF11_R6_R6") (pintype "bidirectional"))
    )
    (net (code "252") (name "unconnected-(U12F-PF12_P6-PadP6)") (class "Default")
      (node (ref "U12") (pin "P6") (pinfunction "PF12_P6_P6") (pintype "bidirectional"))
    )
    (net (code "253") (name "unconnected-(U12F-PF13_N6-PadN6)") (class "Default")
      (node (ref "U12") (pin "N6") (pinfunction "PF13_N6_N6") (pintype "bidirectional"))
    )
    (net (code "254") (name "unconnected-(U12F-PF14_R7-PadR7)") (class "Default")
      (node (ref "U12") (pin "R7") (pinfunction "PF14_R7_R7") (pintype "bidirectional"))
    )
    (net (code "255") (name "unconnected-(U12F-PF15_P7-PadP7)") (class "Default")
      (node (ref "U12") (pin "P7") (pinfunction "PF15_P7_P7") (pintype "bidirectional"))
    )
    (net (code "256") (name "unconnected-(U12G-PG0_N7-PadN7)") (class "Default")
      (node (ref "U12") (pin "N7") (pinfunction "PG0_N7_N7") (pintype "bidirectional"))
    )
    (net (code "257") (name "unconnected-(U12G-PG1_M7-PadM7)") (class "Default")
      (node (ref "U12") (pin "M7") (pinfunction "PG1_M7_M7") (pintype "bidirectional"))
    )
    (net (code "258") (name "unconnected-(U12G-PG2_L15-PadL15)") (class "Default")
      (node (ref "U12") (pin "L15") (pinfunction "PG2_L15_L15") (pintype "bidirectional"))
    )
    (net (code "259") (name "unconnected-(U12G-PG3_K15-PadK15)") (class "Default")
      (node (ref "U12") (pin "K15") (pinfunction "PG3_K15_K15") (pintype "bidirectional"))
    )
    (net (code "260") (name "unconnected-(U12G-PG4_K14-PadK14)") (class "Default")
      (node (ref "U12") (pin "K14") (pinfunction "PG4_K14_K14") (pintype "bidirectional"))
    )
    (net (code "261") (name "unconnected-(U12G-PG5_K13-PadK13)") (class "Default")
      (node (ref "U12") (pin "K13") (pinfunction "PG5_K13_K13") (pintype "bidirectional"))
    )
    (net (code "262") (name "unconnected-(U12G-PG8_H14-PadH14)") (class "Default")
      (node (ref "U12") (pin "H14") (pinfunction "PG8_H14_H14") (pintype "bidirectional"))
    )
    (net (code "263") (name "unconnected-(U12G-PG10_B10-PadB10)") (class "Default")
      (node (ref "U12") (pin "B10") (pinfunction "PG10_B10_B10") (pintype "bidirectional"))
    )
    (net (code "264") (name "unconnected-(U12G-PG11_B9-PadB9)") (class "Default")
      (node (ref "U12") (pin "B9") (pinfunction "PG11_B9_B9") (pintype "bidirectional"))
    )
    (net (code "265") (name "unconnected-(U12G-PG12_B8-PadB8)") (class "Default")
      (node (ref "U12") (pin "B8") (pinfunction "PG12_B8_B8") (pintype "bidirectional"))
    )
    (net (code "266") (name "unconnected-(U12G-PG13_A8-PadA8)") (class "Default")
      (node (ref "U12") (pin "A8") (pinfunction "PG13_A8_A8") (pintype "bidirectional"))
    )
    (net (code "267") (name "unconnected-(U12G-PG15_B7-PadB7)") (class "Default")
      (node (ref "U12") (pin "B7") (pinfunction "PG15_B7_B7") (pintype "bidirectional"))
    )
    (net (code "268") (name "unconnected-(U12H-PH1_H1-PadH1)") (class "Default")
      (node (ref "U12") (pin "H1") (pinfunction "PH1_H1_H1") (pintype "bidirectional"))
    )
    (net (code "269") (name "unconnected-(U12H-PH4_H4-PadH4)") (class "Default")
      (node (ref "U12") (pin "H4") (pinfunction "PH4_H4_H4") (pintype "bidirectional"))
    )
    (net (code "270") (name "unconnected-(U12H-PH5_J4-PadJ4)") (class "Default")
      (node (ref "U12") (pin "J4") (pinfunction "PH5_J4_J4") (pintype "bidirectional"))
    )
    (net (code "271") (name "unconnected-(U12H-PH6_M11-PadM11)") (class "Default")
      (node (ref "U12") (pin "M11") (pinfunction "PH6_M11_M11") (pintype "bidirectional"))
    )
    (net (code "272") (name "unconnected-(U12H-PH7_N12-PadN12)") (class "Default")
      (node (ref "U12") (pin "N12") (pinfunction "PH7_N12_N12") (pintype "bidirectional"))
    )
    (net (code "273") (name "unconnected-(U12H-PH8_M12-PadM12)") (class "Default")
      (node (ref "U12") (pin "M12") (pinfunction "PH8_M12_M12") (pintype "bidirectional"))
    )
    (net (code "274") (name "unconnected-(U12H-PH9_M13-PadM13)") (class "Default")
      (node (ref "U12") (pin "M13") (pinfunction "PH9_M13_M13") (pintype "bidirectional"))
    )
    (net (code "275") (name "unconnected-(U12H-PH10_L13-PadL13)") (class "Default")
      (node (ref "U12") (pin "L13") (pinfunction "PH10_L13_L13") (pintype "bidirectional"))
    )
    (net (code "276") (name "unconnected-(U12H-PH11_L12-PadL12)") (class "Default")
      (node (ref "U12") (pin "L12") (pinfunction "PH11_L12_L12") (pintype "bidirectional"))
    )
    (net (code "277") (name "unconnected-(U12H-PH12_K12-PadK12)") (class "Default")
      (node (ref "U12") (pin "K12") (pinfunction "PH12_K12_K12") (pintype "bidirectional"))
    )
    (net (code "278") (name "unconnected-(U12H-PH13_E12-PadE12)") (class "Default")
      (node (ref "U12") (pin "E12") (pinfunction "PH13_E12_E12") (pintype "bidirectional"))
    )
    (net (code "279") (name "unconnected-(U12H-PH14_E13-PadE13)") (class "Default")
      (node (ref "U12") (pin "E13") (pinfunction "PH14_E13_E13") (pintype "bidirectional"))
    )
    (net (code "280") (name "unconnected-(U12H-PH15_D13-PadD13)") (class "Default")
      (node (ref "U12") (pin "D13") (pinfunction "PH15_D13_D13") (pintype "bidirectional"))
    )
    (net (code "281") (name "unconnected-(U12I-PI0_E14-PadE14)") (class "Default")
      (node (ref "U12") (pin "E14") (pinfunction "PI0_E14_E14") (pintype "bidirectional"))
    )
    (net (code "282") (name "unconnected-(U12I-PI1_D14-PadD14)") (class "Default")
      (node (ref "U12") (pin "D14") (pinfunction "PI1_D14_D14") (pintype "bidirectional"))
    )
    (net (code "283") (name "unconnected-(U12I-PI2_C14-PadC14)") (class "Default")
      (node (ref "U12") (pin "C14") (pinfunction "PI2_C14_C14") (pintype "bidirectional"))
    )
    (net (code "284") (name "unconnected-(U12I-PI3_C13-PadC13)") (class "Default")
      (node (ref "U12") (pin "C13") (pinfunction "PI3_C13_C13") (pintype "bidirectional"))
    )
    (net (code "285") (name "unconnected-(U12I-PI4_D4-PadD4)") (class "Default")
      (node (ref "U12") (pin "D4") (pinfunction "PI4_D4_D4") (pintype "bidirectional"))
    )
    (net (code "286") (name "unconnected-(U12I-PI5_C4-PadC4)") (class "Default")
      (node (ref "U12") (pin "C4") (pinfunction "PI5_C4_C4") (pintype "bidirectional"))
    )
    (net (code "287") (name "unconnected-(U12I-PI8_D2-PadD2)") (class "Default")
      (node (ref "U12") (pin "D2") (pinfunction "PI8_D2_D2") (pintype "bidirectional"))
    )
    (net (code "288") (name "unconnected-(U12I-PI9_D3-PadD3)") (class "Default")
      (node (ref "U12") (pin "D3") (pinfunction "PI9_D3_D3") (pintype "bidirectional"))
    )
    (net (code "289") (name "unconnected-(U12I-PI10_E3-PadE3)") (class "Default")
      (node (ref "U12") (pin "E3") (pinfunction "PI10_E3_E3") (pintype "bidirectional"))
    )
    (net (code "290") (name "unconnected-(U12I-PI11_E4-PadE4)") (class "Default")
      (node (ref "U12") (pin "E4") (pinfunction "PI11_E4_E4") (pintype "bidirectional"))
    )
    (net (code "291") (name "unconnected-(U13-ID-Pad3)") (class "Default")
      (node (ref "U13") (pin "3") (pinfunction "ID_3") (pintype "bidirectional"))
    )
  )
)
